# ALU.net
KiCad netlist of a schematic drawn in EAGLE
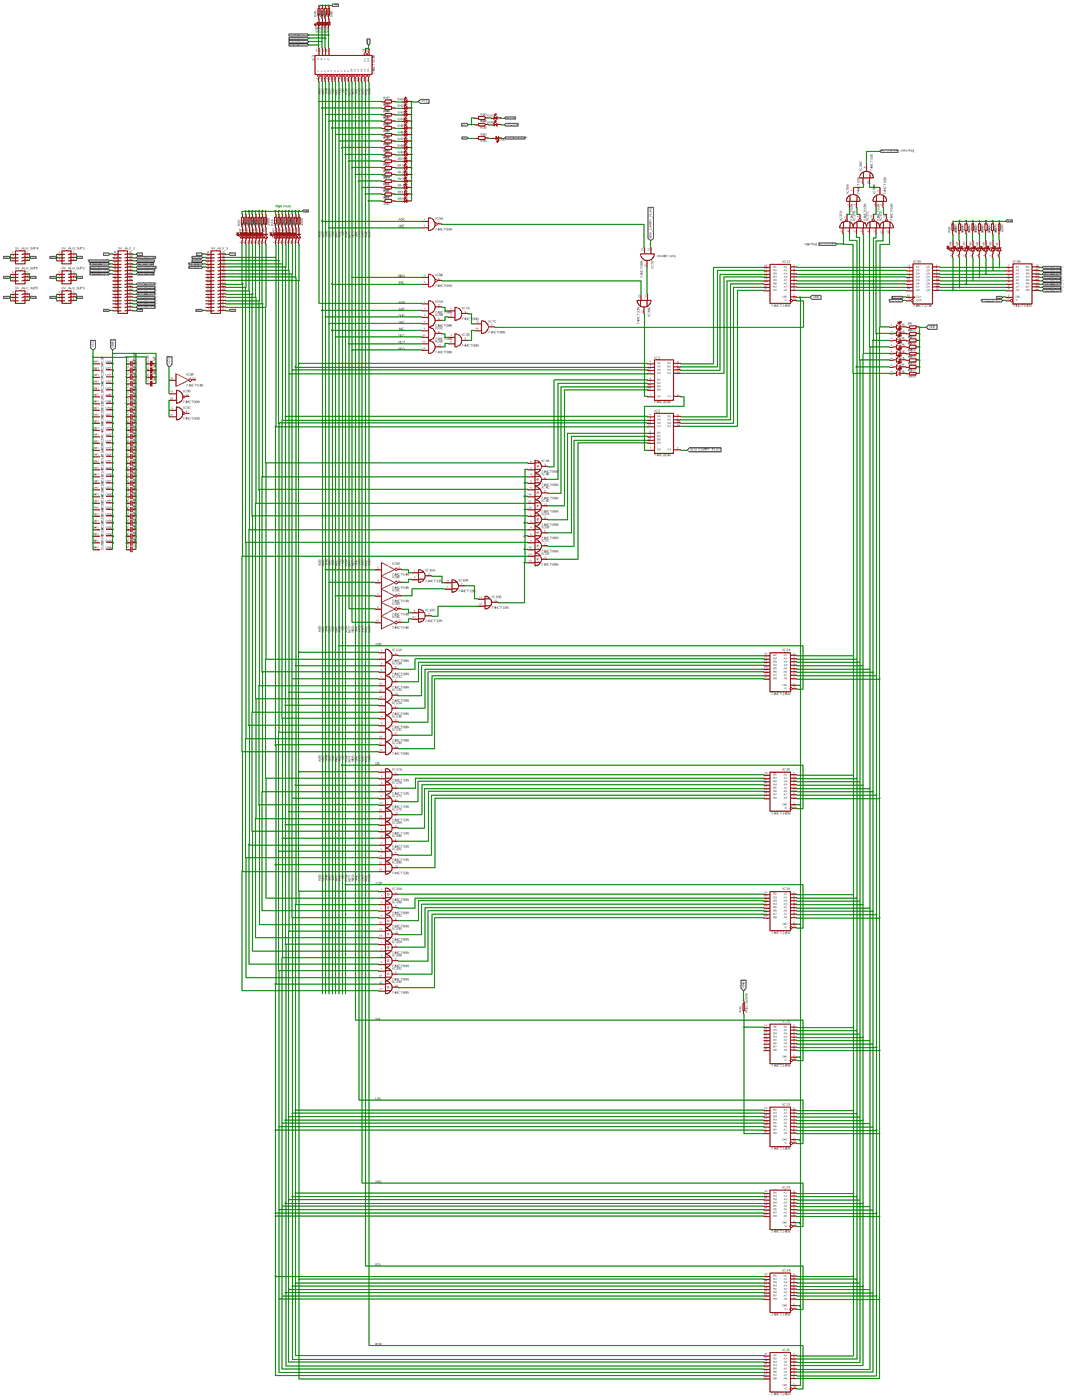
[diagram p0: schematic, sheet 1, overview]
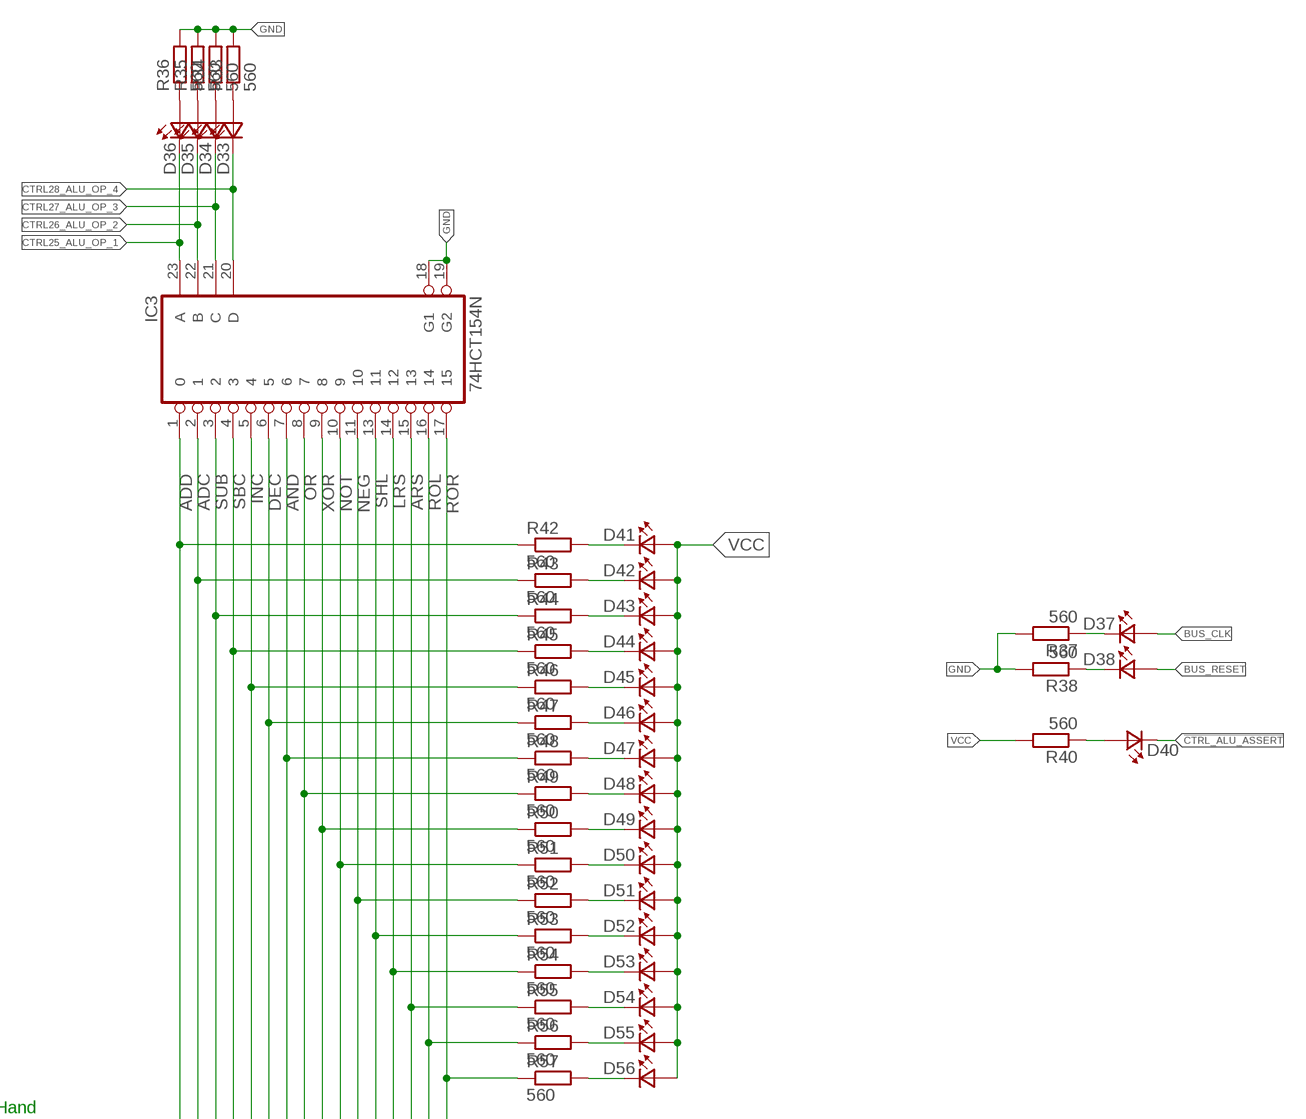
[diagram p1: schematic, sheet 1, part 1 of 8]
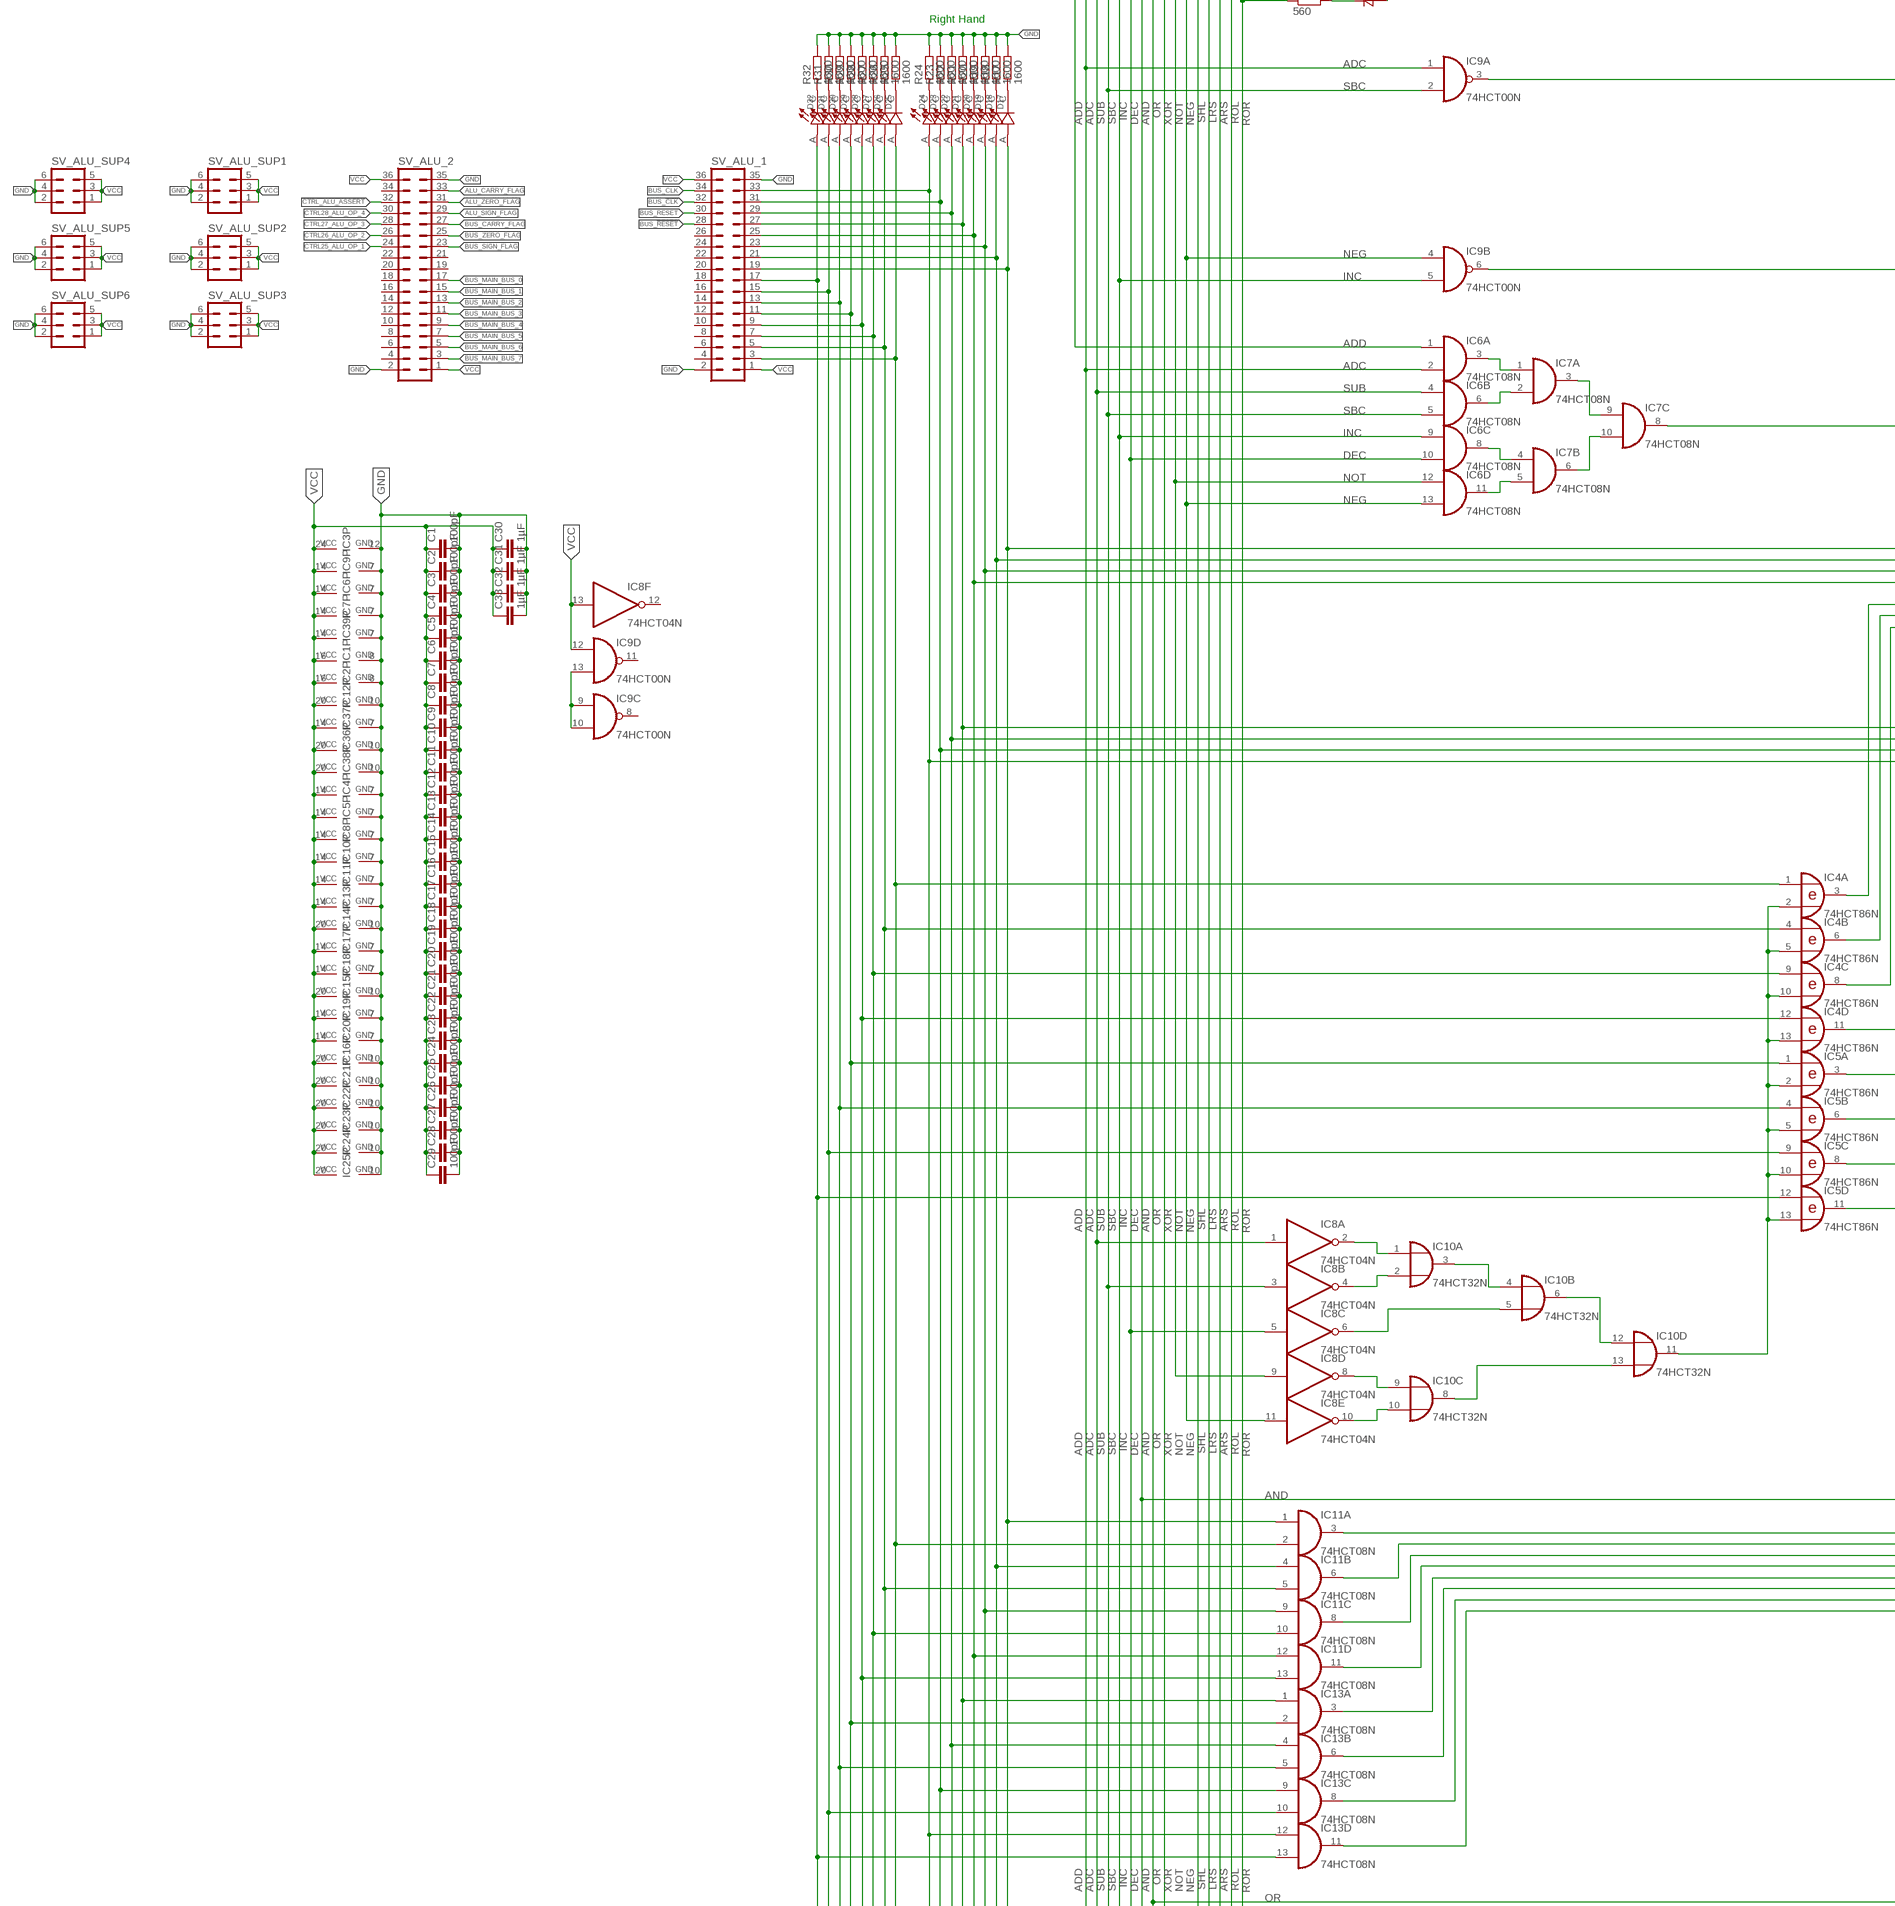
[diagram p2: schematic, sheet 1, part 2 of 8]
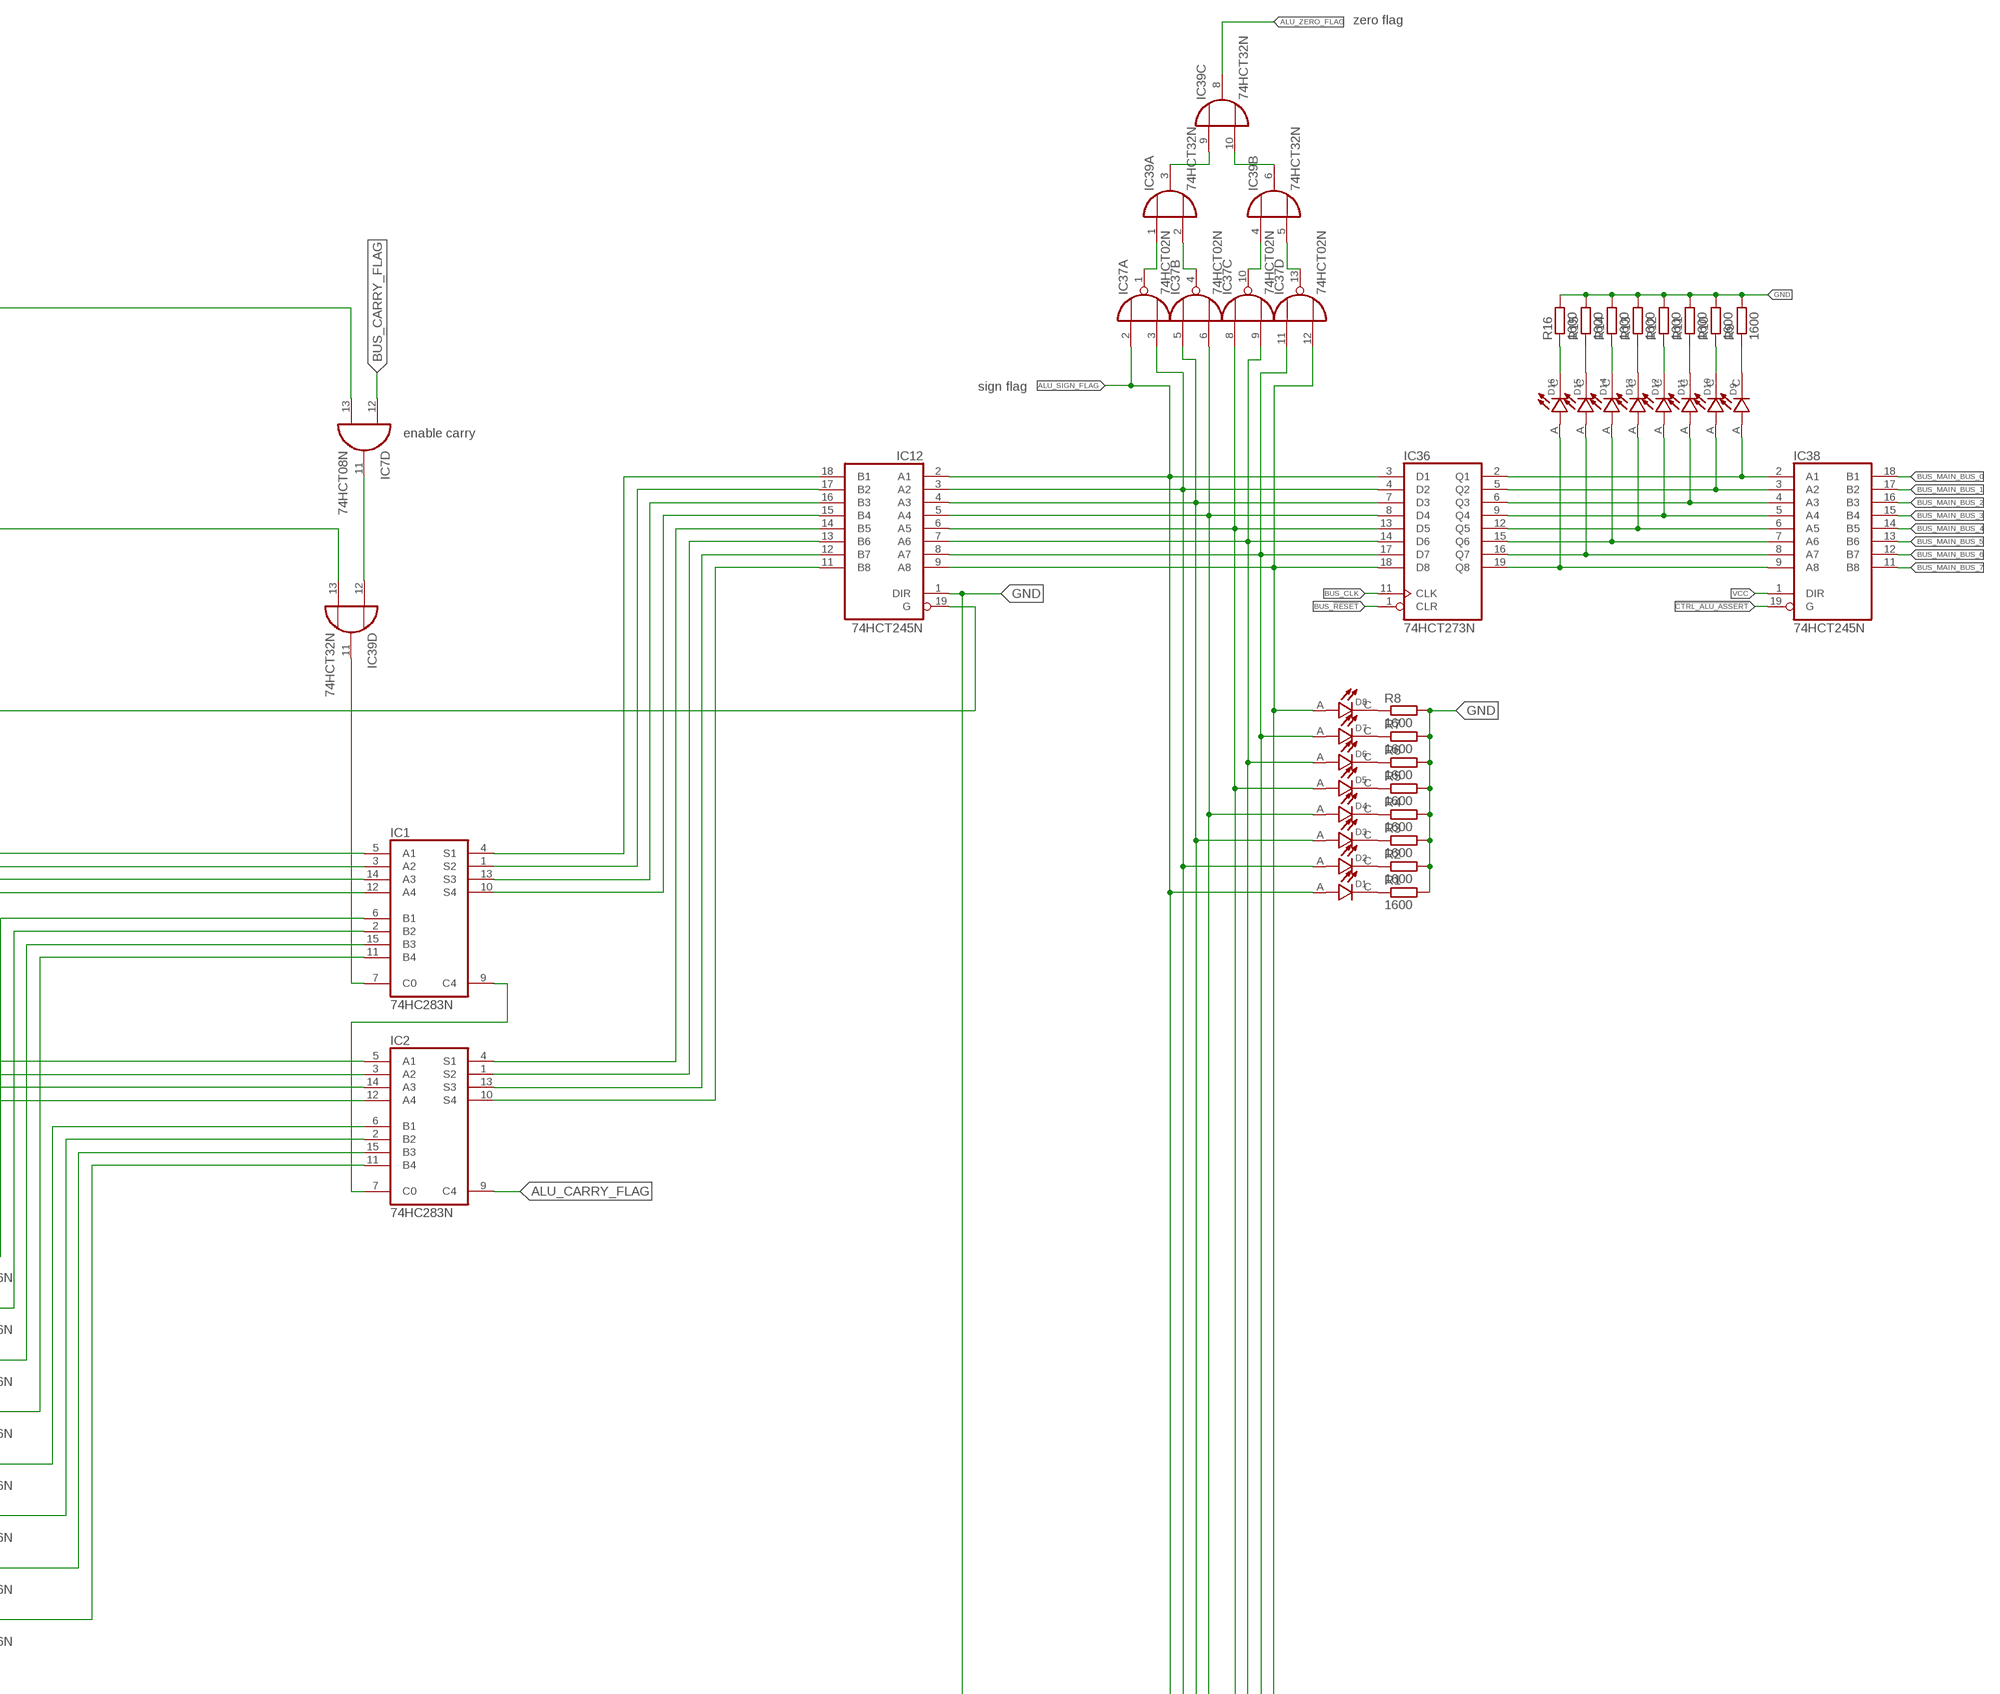
[diagram p3: schematic, sheet 1, part 3 of 8]
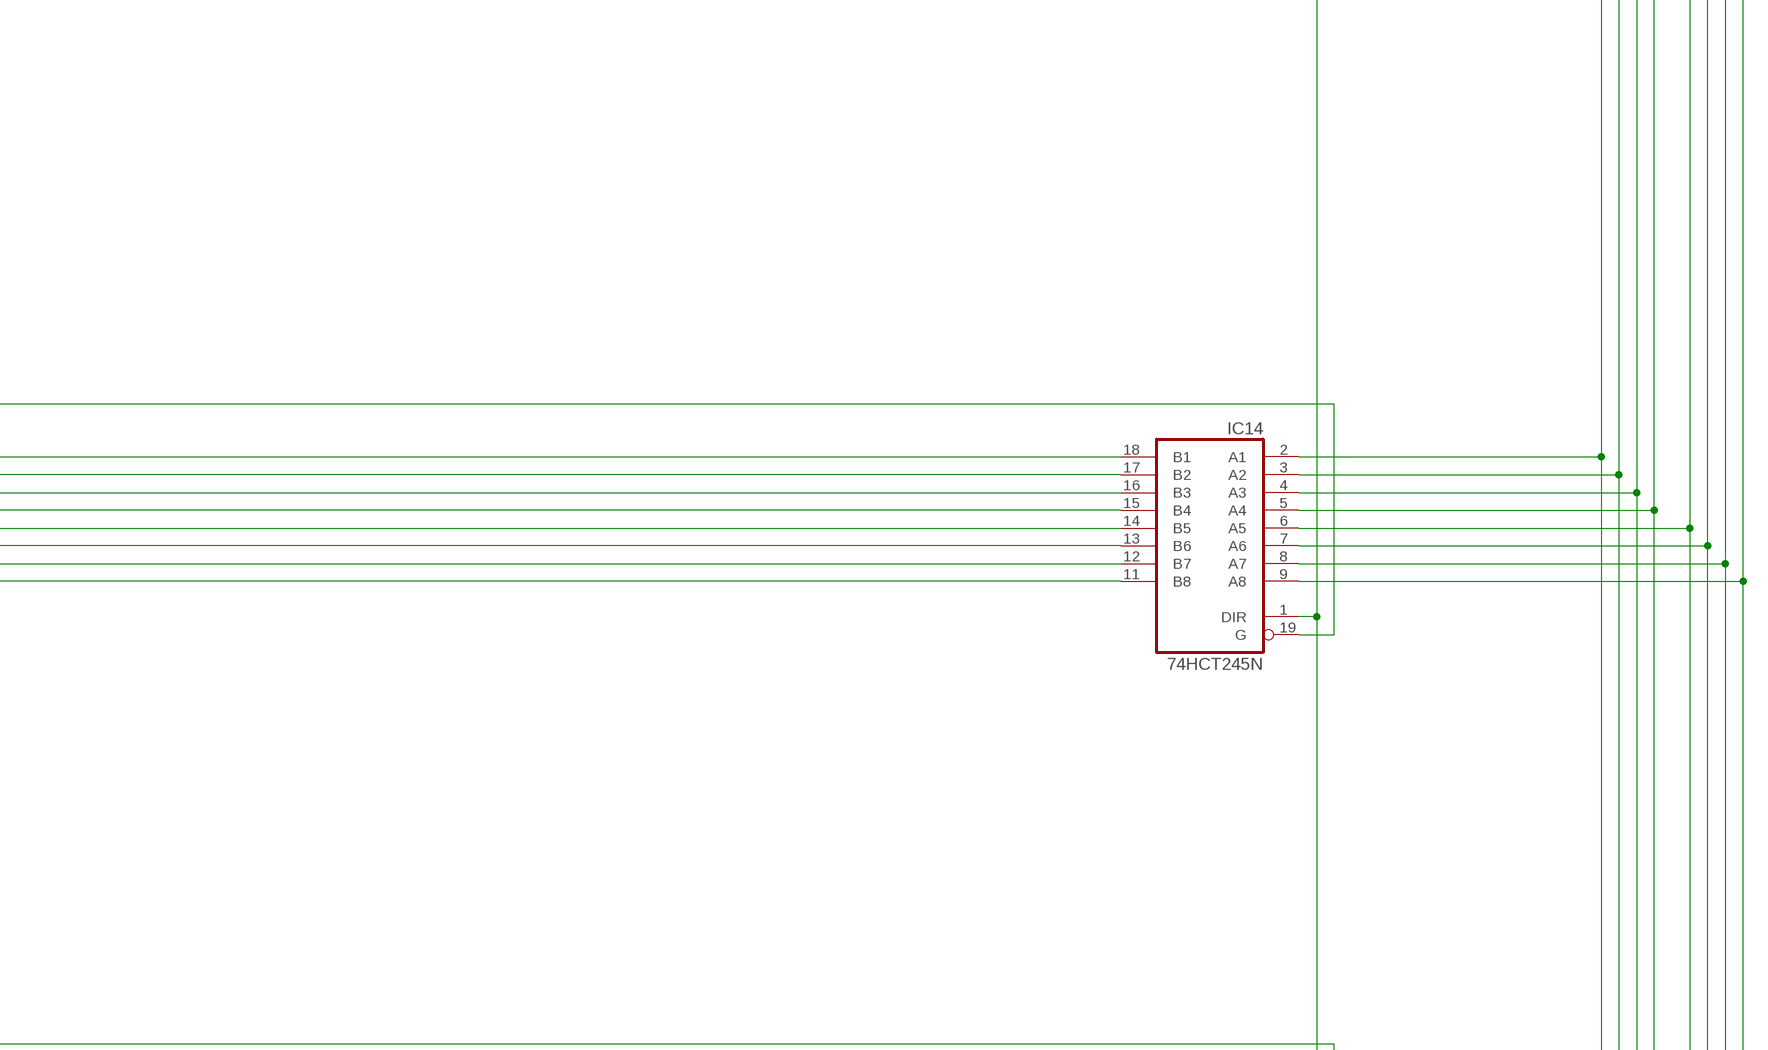
[diagram p4: schematic, sheet 1, part 4 of 8]
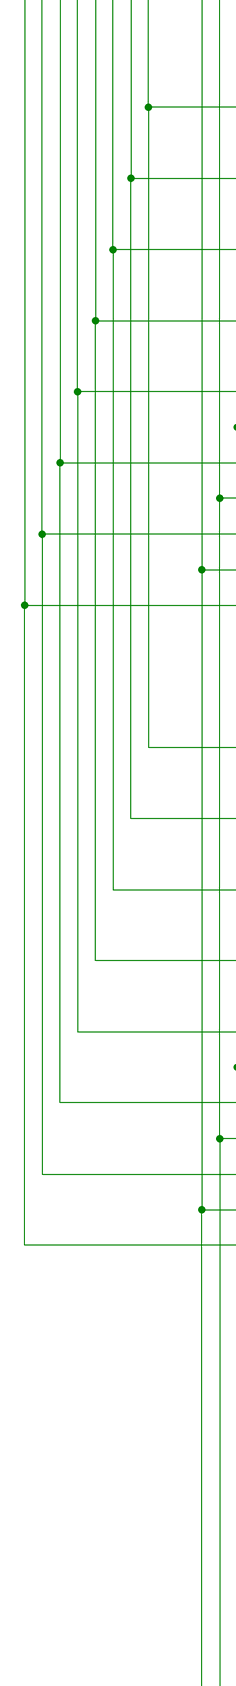
[diagram p5: schematic, sheet 1, part 5 of 8]
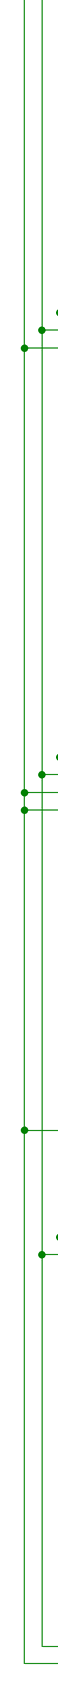
[diagram p6: schematic, sheet 1, part 6 of 8]
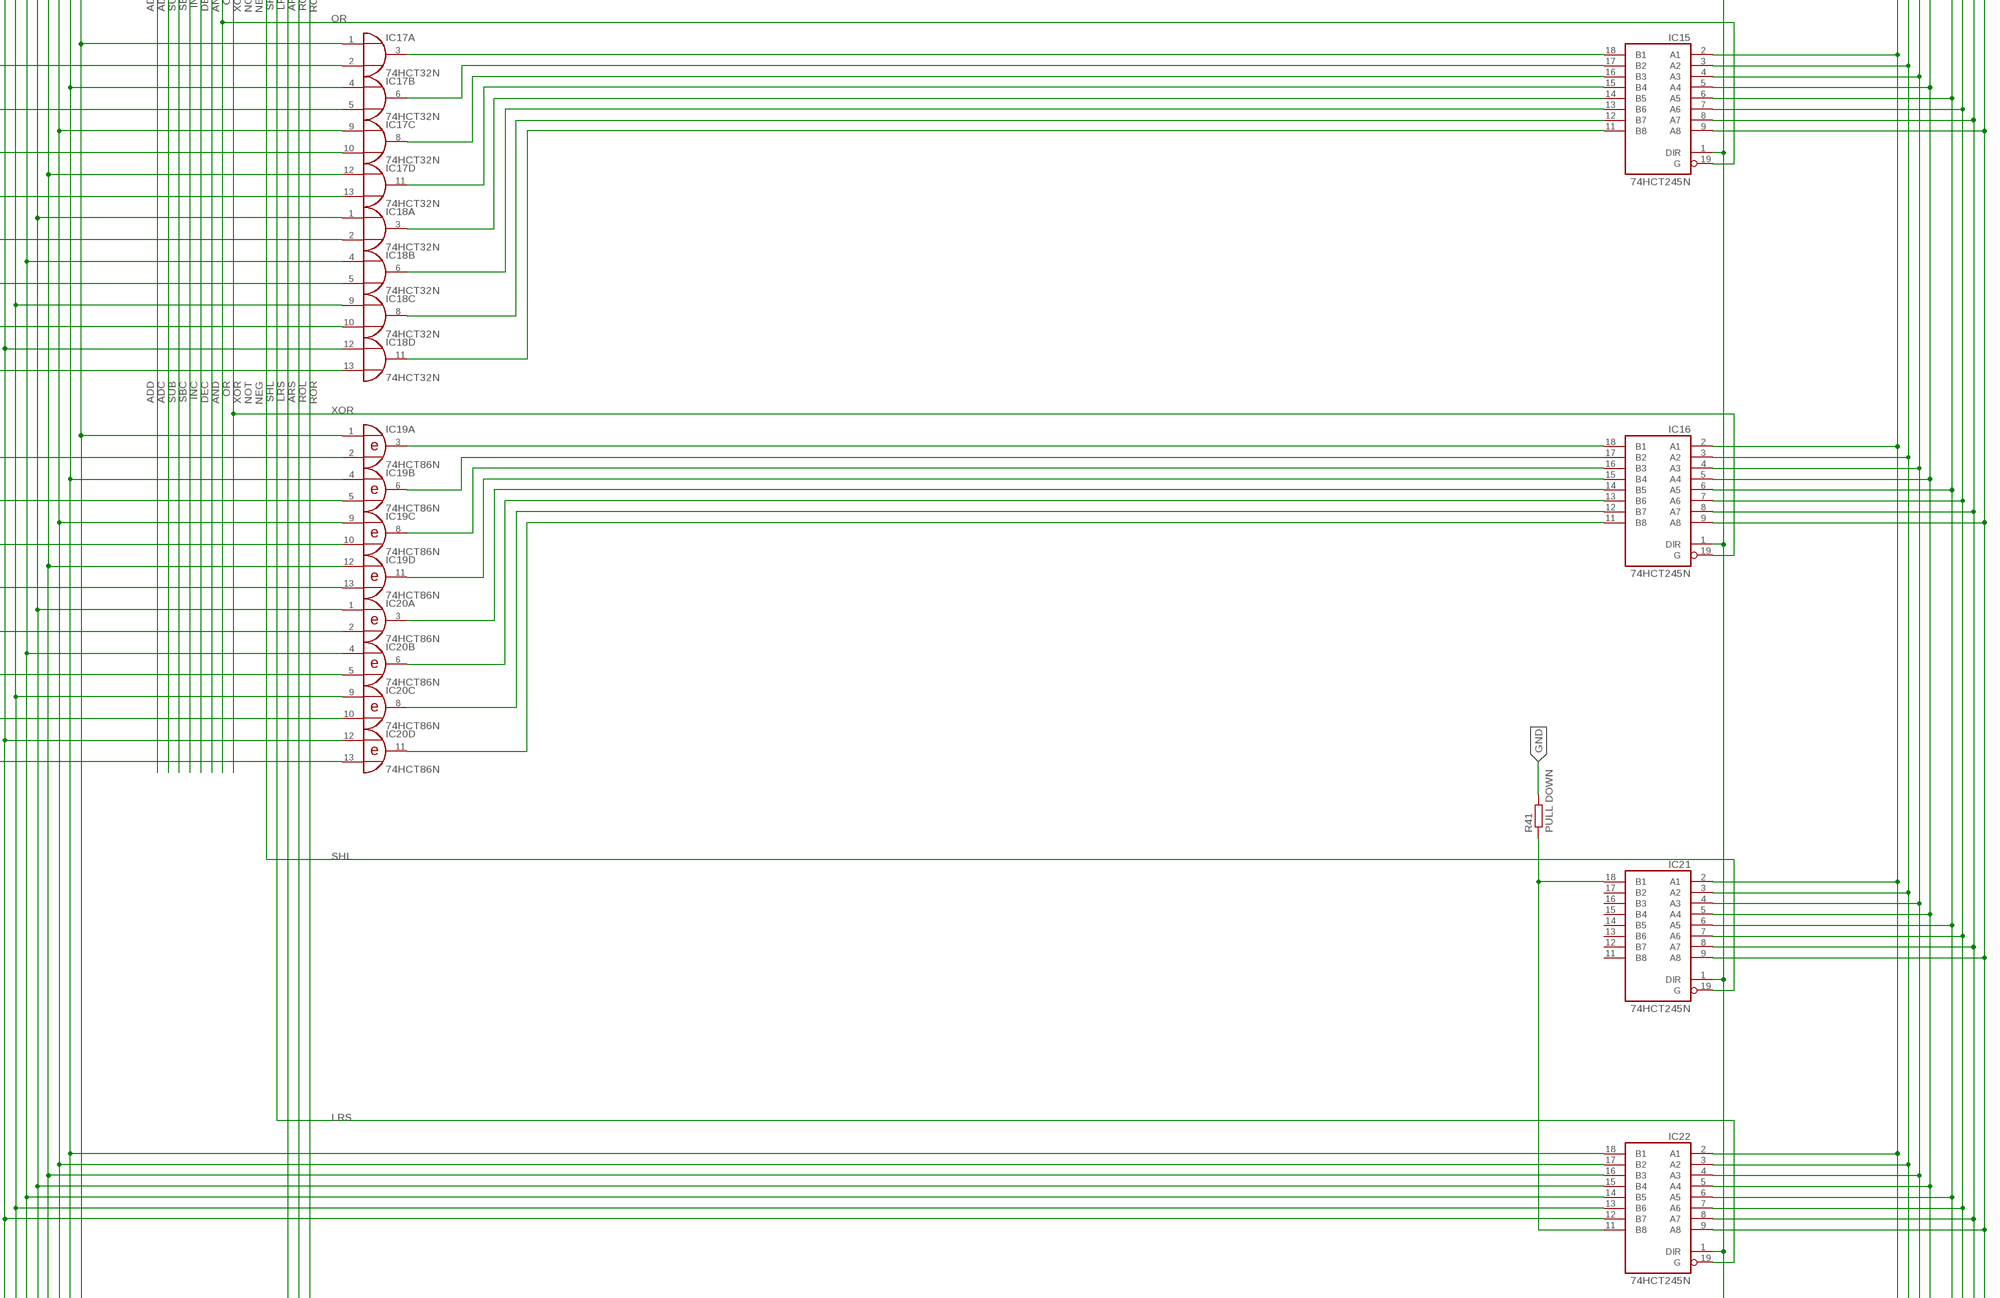
[diagram p7: schematic, sheet 1, part 7 of 8]
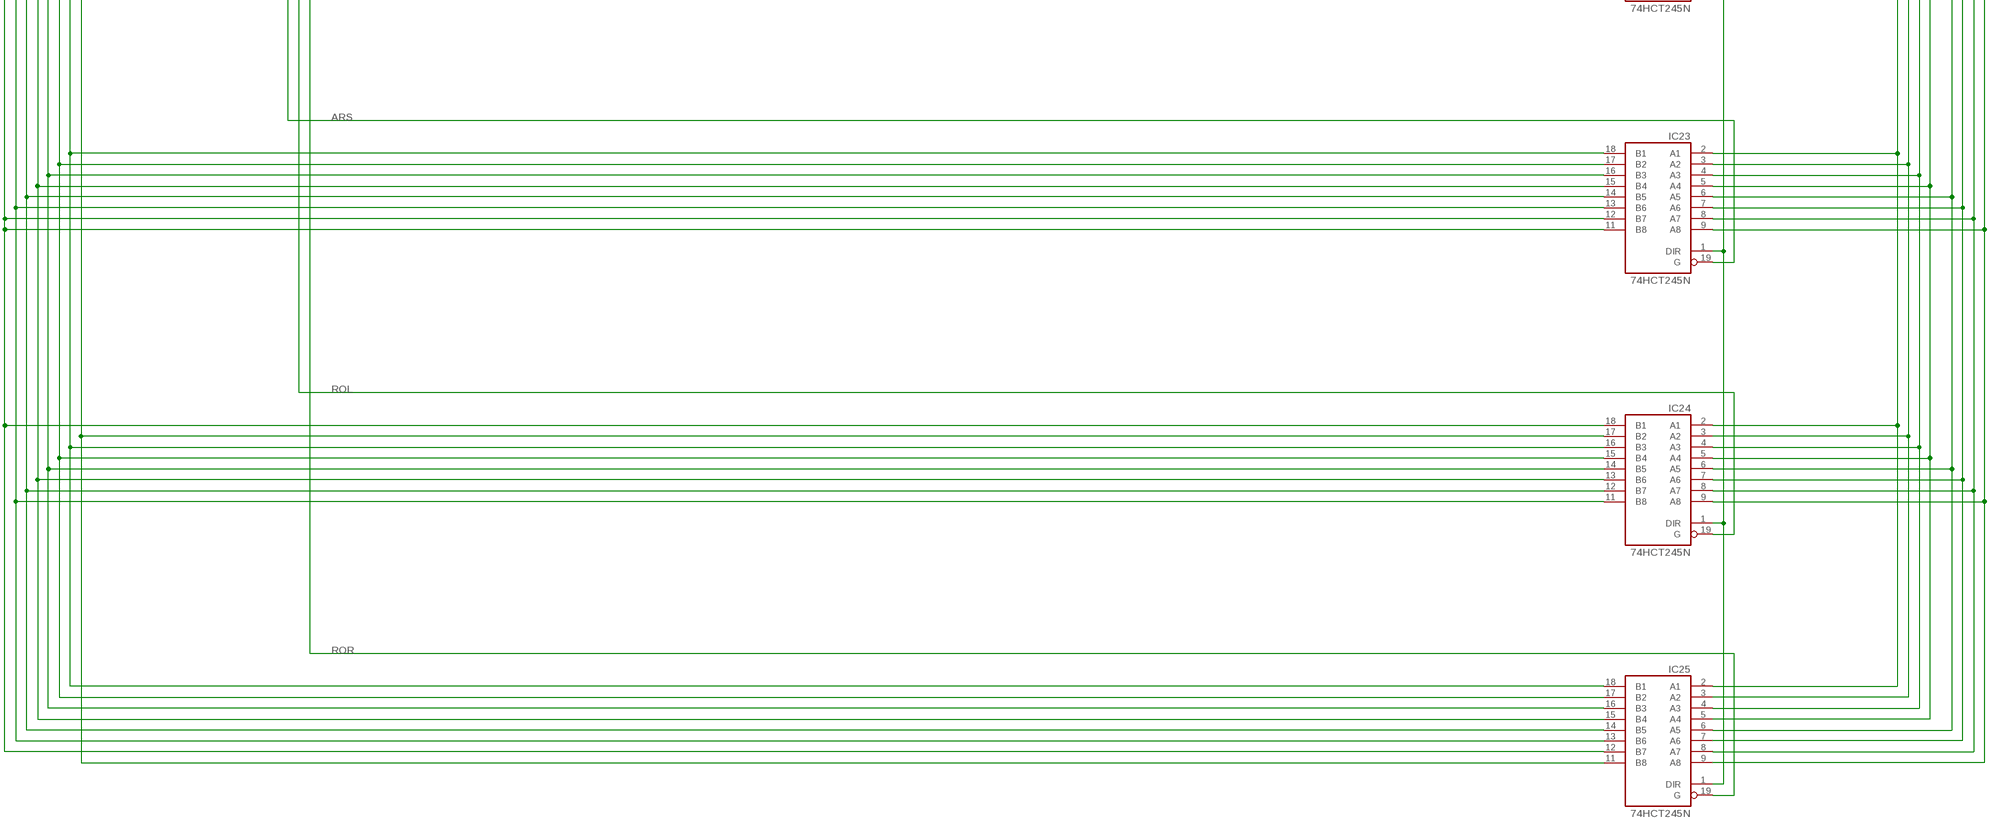
[diagram p8: schematic, sheet 1, part 8 of 8]

(export (version "E")
  (design (tool "Eeschema 10.0.6"))
  (components
    (comp (ref "C1")
      (value "100pF")
      (footprint "eagle-import:C0805")
      (libsource (lib "eagle-import") (part "C-EUC0805"))
    )
    (comp (ref "C2")
      (value "100pF")
      (footprint "eagle-import:C0805")
      (libsource (lib "eagle-import") (part "C-EUC0805"))
    )
    (comp (ref "C3")
      (value "100pF")
      (footprint "eagle-import:C0805")
      (libsource (lib "eagle-import") (part "C-EUC0805"))
    )
    (comp (ref "C4")
      (value "100pF")
      (footprint "eagle-import:C0805")
      (libsource (lib "eagle-import") (part "C-EUC0805"))
    )
    (comp (ref "C5")
      (value "100pF")
      (footprint "eagle-import:C0805")
      (libsource (lib "eagle-import") (part "C-EUC0805"))
    )
    (comp (ref "C6")
      (value "100pF")
      (footprint "eagle-import:C0805")
      (libsource (lib "eagle-import") (part "C-EUC0805"))
    )
    (comp (ref "C7")
      (value "100pF")
      (footprint "eagle-import:C0805")
      (libsource (lib "eagle-import") (part "C-EUC0805"))
    )
    (comp (ref "C8")
      (value "100pF")
      (footprint "eagle-import:C0805")
      (libsource (lib "eagle-import") (part "C-EUC0805"))
    )
    (comp (ref "C9")
      (value "100pF")
      (footprint "eagle-import:C0805")
      (libsource (lib "eagle-import") (part "C-EUC0805"))
    )
    (comp (ref "C10")
      (value "100pF")
      (footprint "eagle-import:C0805")
      (libsource (lib "eagle-import") (part "C-EUC0805"))
    )
    (comp (ref "C11")
      (value "100pF")
      (footprint "eagle-import:C0805")
      (libsource (lib "eagle-import") (part "C-EUC0805"))
    )
    (comp (ref "C12")
      (value "100pF")
      (footprint "eagle-import:C0805")
      (libsource (lib "eagle-import") (part "C-EUC0805"))
    )
    (comp (ref "C13")
      (value "100pF")
      (footprint "eagle-import:C0805")
      (libsource (lib "eagle-import") (part "C-EUC0805"))
    )
    (comp (ref "C14")
      (value "100pF")
      (footprint "eagle-import:C0805")
      (libsource (lib "eagle-import") (part "C-EUC0805"))
    )
    (comp (ref "C15")
      (value "100pF")
      (footprint "eagle-import:C0805")
      (libsource (lib "eagle-import") (part "C-EUC0805"))
    )
    (comp (ref "C16")
      (value "100pF")
      (footprint "eagle-import:C0805")
      (libsource (lib "eagle-import") (part "C-EUC0805"))
    )
    (comp (ref "C17")
      (value "100pF")
      (footprint "eagle-import:C0805")
      (libsource (lib "eagle-import") (part "C-EUC0805"))
    )
    (comp (ref "C18")
      (value "100pF")
      (footprint "eagle-import:C0805")
      (libsource (lib "eagle-import") (part "C-EUC0805"))
    )
    (comp (ref "C19")
      (value "100pF")
      (footprint "eagle-import:C0805")
      (libsource (lib "eagle-import") (part "C-EUC0805"))
    )
    (comp (ref "C20")
      (value "100pF")
      (footprint "eagle-import:C0805")
      (libsource (lib "eagle-import") (part "C-EUC0805"))
    )
    (comp (ref "C21")
      (value "100pF")
      (footprint "eagle-import:C0805")
      (libsource (lib "eagle-import") (part "C-EUC0805"))
    )
    (comp (ref "C22")
      (value "100pF")
      (footprint "eagle-import:C0805")
      (libsource (lib "eagle-import") (part "C-EUC0805"))
    )
    (comp (ref "C23")
      (value "100pF")
      (footprint "eagle-import:C0805")
      (libsource (lib "eagle-import") (part "C-EUC0805"))
    )
    (comp (ref "C24")
      (value "100pF")
      (footprint "eagle-import:C0805")
      (libsource (lib "eagle-import") (part "C-EUC0805"))
    )
    (comp (ref "C25")
      (value "100pF")
      (footprint "eagle-import:C0805")
      (libsource (lib "eagle-import") (part "C-EUC0805"))
    )
    (comp (ref "C26")
      (value "100pF")
      (footprint "eagle-import:C0805")
      (libsource (lib "eagle-import") (part "C-EUC0805"))
    )
    (comp (ref "C27")
      (value "100pF")
      (footprint "eagle-import:C0805")
      (libsource (lib "eagle-import") (part "C-EUC0805"))
    )
    (comp (ref "C28")
      (value "100pF")
      (footprint "eagle-import:C0805")
      (libsource (lib "eagle-import") (part "C-EUC0805"))
    )
    (comp (ref "C29")
      (value "100pF")
      (footprint "eagle-import:C0805")
      (libsource (lib "eagle-import") (part "C-EUC0805"))
    )
    (comp (ref "C30")
      (value "1µF")
      (footprint "eagle-import:C0805")
      (libsource (lib "eagle-import") (part "C-EUC0805"))
    )
    (comp (ref "C31")
      (value "1µF")
      (footprint "eagle-import:C0805")
      (libsource (lib "eagle-import") (part "C-EUC0805"))
    )
    (comp (ref "C32")
      (value "1µF")
      (footprint "eagle-import:C0805")
      (libsource (lib "eagle-import") (part "C-EUC0805"))
    )
    (comp (ref "C33")
      (value "1µF")
      (footprint "eagle-import:C0805")
      (libsource (lib "eagle-import") (part "C-EUC0805"))
    )
    (comp (ref "D1")
      (value "LTST-C193KRKT-5A")
      (footprint "eagle-import:LEDC1608X45N")
      (fields (field (name "MANUFACTURER") "Lite-On"))
      (libsource (lib "eagle-import") (part "LTST-C193KRKT-5A"))
    )
    (comp (ref "D2")
      (value "LTST-C193KRKT-5A")
      (footprint "eagle-import:LEDC1608X45N")
      (fields (field (name "MANUFACTURER") "Lite-On"))
      (libsource (lib "eagle-import") (part "LTST-C193KRKT-5A"))
    )
    (comp (ref "D3")
      (value "LTST-C193KRKT-5A")
      (footprint "eagle-import:LEDC1608X45N")
      (fields (field (name "MANUFACTURER") "Lite-On"))
      (libsource (lib "eagle-import") (part "LTST-C193KRKT-5A"))
    )
    (comp (ref "D4")
      (value "LTST-C193KRKT-5A")
      (footprint "eagle-import:LEDC1608X45N")
      (fields (field (name "MANUFACTURER") "Lite-On"))
      (libsource (lib "eagle-import") (part "LTST-C193KRKT-5A"))
    )
    (comp (ref "D5")
      (value "LTST-C193KRKT-5A")
      (footprint "eagle-import:LEDC1608X45N")
      (fields (field (name "MANUFACTURER") "Lite-On"))
      (libsource (lib "eagle-import") (part "LTST-C193KRKT-5A"))
    )
    (comp (ref "D6")
      (value "LTST-C193KRKT-5A")
      (footprint "eagle-import:LEDC1608X45N")
      (fields (field (name "MANUFACTURER") "Lite-On"))
      (libsource (lib "eagle-import") (part "LTST-C193KRKT-5A"))
    )
    (comp (ref "D7")
      (value "LTST-C193KRKT-5A")
      (footprint "eagle-import:LEDC1608X45N")
      (fields (field (name "MANUFACTURER") "Lite-On"))
      (libsource (lib "eagle-import") (part "LTST-C193KRKT-5A"))
    )
    (comp (ref "D8")
      (value "LTST-C193KRKT-5A")
      (footprint "eagle-import:LEDC1608X45N")
      (fields (field (name "MANUFACTURER") "Lite-On"))
      (libsource (lib "eagle-import") (part "LTST-C193KRKT-5A"))
    )
    (comp (ref "D9")
      (value "LTST-C193KRKT-5A")
      (footprint "eagle-import:LEDC1608X45N")
      (fields (field (name "MANUFACTURER") "Lite-On"))
      (libsource (lib "eagle-import") (part "LTST-C193KRKT-5A"))
    )
    (comp (ref "D10")
      (value "LTST-C193KRKT-5A")
      (footprint "eagle-import:LEDC1608X45N")
      (fields (field (name "MANUFACTURER") "Lite-On"))
      (libsource (lib "eagle-import") (part "LTST-C193KRKT-5A"))
    )
    (comp (ref "D11")
      (value "LTST-C193KRKT-5A")
      (footprint "eagle-import:LEDC1608X45N")
      (fields (field (name "MANUFACTURER") "Lite-On"))
      (libsource (lib "eagle-import") (part "LTST-C193KRKT-5A"))
    )
    (comp (ref "D12")
      (value "LTST-C193KRKT-5A")
      (footprint "eagle-import:LEDC1608X45N")
      (fields (field (name "MANUFACTURER") "Lite-On"))
      (libsource (lib "eagle-import") (part "LTST-C193KRKT-5A"))
    )
    (comp (ref "D13")
      (value "LTST-C193KRKT-5A")
      (footprint "eagle-import:LEDC1608X45N")
      (fields (field (name "MANUFACTURER") "Lite-On"))
      (libsource (lib "eagle-import") (part "LTST-C193KRKT-5A"))
    )
    (comp (ref "D14")
      (value "LTST-C193KRKT-5A")
      (footprint "eagle-import:LEDC1608X45N")
      (fields (field (name "MANUFACTURER") "Lite-On"))
      (libsource (lib "eagle-import") (part "LTST-C193KRKT-5A"))
    )
    (comp (ref "D15")
      (value "LTST-C193KRKT-5A")
      (footprint "eagle-import:LEDC1608X45N")
      (fields (field (name "MANUFACTURER") "Lite-On"))
      (libsource (lib "eagle-import") (part "LTST-C193KRKT-5A"))
    )
    (comp (ref "D16")
      (value "LTST-C193KRKT-5A")
      (footprint "eagle-import:LEDC1608X45N")
      (fields (field (name "MANUFACTURER") "Lite-On"))
      (libsource (lib "eagle-import") (part "LTST-C193KRKT-5A"))
    )
    (comp (ref "D17")
      (value "LTST-C193KRKT-5A")
      (footprint "eagle-import:LEDC1608X45N")
      (fields (field (name "MANUFACTURER") "Lite-On"))
      (libsource (lib "eagle-import") (part "LTST-C193KRKT-5A"))
    )
    (comp (ref "D18")
      (value "LTST-C193KRKT-5A")
      (footprint "eagle-import:LEDC1608X45N")
      (fields (field (name "MANUFACTURER") "Lite-On"))
      (libsource (lib "eagle-import") (part "LTST-C193KRKT-5A"))
    )
    (comp (ref "D19")
      (value "LTST-C193KRKT-5A")
      (footprint "eagle-import:LEDC1608X45N")
      (fields (field (name "MANUFACTURER") "Lite-On"))
      (libsource (lib "eagle-import") (part "LTST-C193KRKT-5A"))
    )
    (comp (ref "D20")
      (value "LTST-C193KRKT-5A")
      (footprint "eagle-import:LEDC1608X45N")
      (fields (field (name "MANUFACTURER") "Lite-On"))
      (libsource (lib "eagle-import") (part "LTST-C193KRKT-5A"))
    )
    (comp (ref "D21")
      (value "LTST-C193KRKT-5A")
      (footprint "eagle-import:LEDC1608X45N")
      (fields (field (name "MANUFACTURER") "Lite-On"))
      (libsource (lib "eagle-import") (part "LTST-C193KRKT-5A"))
    )
    (comp (ref "D22")
      (value "LTST-C193KRKT-5A")
      (footprint "eagle-import:LEDC1608X45N")
      (fields (field (name "MANUFACTURER") "Lite-On"))
      (libsource (lib "eagle-import") (part "LTST-C193KRKT-5A"))
    )
    (comp (ref "D23")
      (value "LTST-C193KRKT-5A")
      (footprint "eagle-import:LEDC1608X45N")
      (fields (field (name "MANUFACTURER") "Lite-On"))
      (libsource (lib "eagle-import") (part "LTST-C193KRKT-5A"))
    )
    (comp (ref "D24")
      (value "LTST-C193KRKT-5A")
      (footprint "eagle-import:LEDC1608X45N")
      (fields (field (name "MANUFACTURER") "Lite-On"))
      (libsource (lib "eagle-import") (part "LTST-C193KRKT-5A"))
    )
    (comp (ref "D25")
      (value "LTST-C193KRKT-5A")
      (footprint "eagle-import:LEDC1608X45N")
      (fields (field (name "MANUFACTURER") "Lite-On"))
      (libsource (lib "eagle-import") (part "LTST-C193KRKT-5A"))
    )
    (comp (ref "D26")
      (value "LTST-C193KRKT-5A")
      (footprint "eagle-import:LEDC1608X45N")
      (fields (field (name "MANUFACTURER") "Lite-On"))
      (libsource (lib "eagle-import") (part "LTST-C193KRKT-5A"))
    )
    (comp (ref "D27")
      (value "LTST-C193KRKT-5A")
      (footprint "eagle-import:LEDC1608X45N")
      (fields (field (name "MANUFACTURER") "Lite-On"))
      (libsource (lib "eagle-import") (part "LTST-C193KRKT-5A"))
    )
    (comp (ref "D28")
      (value "LTST-C193KRKT-5A")
      (footprint "eagle-import:LEDC1608X45N")
      (fields (field (name "MANUFACTURER") "Lite-On"))
      (libsource (lib "eagle-import") (part "LTST-C193KRKT-5A"))
    )
    (comp (ref "D29")
      (value "LTST-C193KRKT-5A")
      (footprint "eagle-import:LEDC1608X45N")
      (fields (field (name "MANUFACTURER") "Lite-On"))
      (libsource (lib "eagle-import") (part "LTST-C193KRKT-5A"))
    )
    (comp (ref "D30")
      (value "LTST-C193KRKT-5A")
      (footprint "eagle-import:LEDC1608X45N")
      (fields (field (name "MANUFACTURER") "Lite-On"))
      (libsource (lib "eagle-import") (part "LTST-C193KRKT-5A"))
    )
    (comp (ref "D31")
      (value "LTST-C193KRKT-5A")
      (footprint "eagle-import:LEDC1608X45N")
      (fields (field (name "MANUFACTURER") "Lite-On"))
      (libsource (lib "eagle-import") (part "LTST-C193KRKT-5A"))
    )
    (comp (ref "D32")
      (value "LTST-C193KRKT-5A")
      (footprint "eagle-import:LEDC1608X45N")
      (fields (field (name "MANUFACTURER") "Lite-On"))
      (libsource (lib "eagle-import") (part "LTST-C193KRKT-5A"))
    )
    (comp (ref "D33")
      (value "LTST-C193TBKT-5A")
      (footprint "eagle-import:0603")
      (libsource (lib "eagle-import") (part "LTST-C193TBKT-5A"))
    )
    (comp (ref "D34")
      (value "LTST-C193TBKT-5A")
      (footprint "eagle-import:0603")
      (libsource (lib "eagle-import") (part "LTST-C193TBKT-5A"))
    )
    (comp (ref "D35")
      (value "LTST-C193TBKT-5A")
      (footprint "eagle-import:0603")
      (libsource (lib "eagle-import") (part "LTST-C193TBKT-5A"))
    )
    (comp (ref "D36")
      (value "LTST-C193TBKT-5A")
      (footprint "eagle-import:0603")
      (libsource (lib "eagle-import") (part "LTST-C193TBKT-5A"))
    )
    (comp (ref "D37")
      (value "LTST-C193TBKT-5A")
      (footprint "eagle-import:0603")
      (libsource (lib "eagle-import") (part "LTST-C193TBKT-5A"))
    )
    (comp (ref "D38")
      (value "LTST-C193TBKT-5A")
      (footprint "eagle-import:0603")
      (libsource (lib "eagle-import") (part "LTST-C193TBKT-5A"))
    )
    (comp (ref "D40")
      (value "LTST-C193TBKT-5A")
      (footprint "eagle-import:0603")
      (libsource (lib "eagle-import") (part "LTST-C193TBKT-5A"))
    )
    (comp (ref "D41")
      (value "LTST-C193TBKT-5A")
      (footprint "eagle-import:0603")
      (libsource (lib "eagle-import") (part "LTST-C193TBKT-5A"))
    )
    (comp (ref "D42")
      (value "LTST-C193TBKT-5A")
      (footprint "eagle-import:0603")
      (libsource (lib "eagle-import") (part "LTST-C193TBKT-5A"))
    )
    (comp (ref "D43")
      (value "LTST-C193TBKT-5A")
      (footprint "eagle-import:0603")
      (libsource (lib "eagle-import") (part "LTST-C193TBKT-5A"))
    )
    (comp (ref "D44")
      (value "LTST-C193TBKT-5A")
      (footprint "eagle-import:0603")
      (libsource (lib "eagle-import") (part "LTST-C193TBKT-5A"))
    )
    (comp (ref "D45")
      (value "LTST-C193TBKT-5A")
      (footprint "eagle-import:0603")
      (libsource (lib "eagle-import") (part "LTST-C193TBKT-5A"))
    )
    (comp (ref "D46")
      (value "LTST-C193TBKT-5A")
      (footprint "eagle-import:0603")
      (libsource (lib "eagle-import") (part "LTST-C193TBKT-5A"))
    )
    (comp (ref "D47")
      (value "LTST-C193TBKT-5A")
      (footprint "eagle-import:0603")
      (libsource (lib "eagle-import") (part "LTST-C193TBKT-5A"))
    )
    (comp (ref "D48")
      (value "LTST-C193TBKT-5A")
      (footprint "eagle-import:0603")
      (libsource (lib "eagle-import") (part "LTST-C193TBKT-5A"))
    )
    (comp (ref "D49")
      (value "LTST-C193TBKT-5A")
      (footprint "eagle-import:0603")
      (libsource (lib "eagle-import") (part "LTST-C193TBKT-5A"))
    )
    (comp (ref "D50")
      (value "LTST-C193TBKT-5A")
      (footprint "eagle-import:0603")
      (libsource (lib "eagle-import") (part "LTST-C193TBKT-5A"))
    )
    (comp (ref "D51")
      (value "LTST-C193TBKT-5A")
      (footprint "eagle-import:0603")
      (libsource (lib "eagle-import") (part "LTST-C193TBKT-5A"))
    )
    (comp (ref "D52")
      (value "LTST-C193TBKT-5A")
      (footprint "eagle-import:0603")
      (libsource (lib "eagle-import") (part "LTST-C193TBKT-5A"))
    )
    (comp (ref "D53")
      (value "LTST-C193TBKT-5A")
      (footprint "eagle-import:0603")
      (libsource (lib "eagle-import") (part "LTST-C193TBKT-5A"))
    )
    (comp (ref "D54")
      (value "LTST-C193TBKT-5A")
      (footprint "eagle-import:0603")
      (libsource (lib "eagle-import") (part "LTST-C193TBKT-5A"))
    )
    (comp (ref "D55")
      (value "LTST-C193TBKT-5A")
      (footprint "eagle-import:0603")
      (libsource (lib "eagle-import") (part "LTST-C193TBKT-5A"))
    )
    (comp (ref "D56")
      (value "LTST-C193TBKT-5A")
      (footprint "eagle-import:0603")
      (libsource (lib "eagle-import") (part "LTST-C193TBKT-5A"))
    )
    (comp (ref "IC1")
      (value "74HC283N")
      (footprint "eagle-import:DIL16")
      (libsource (lib "eagle-import") (part "74283NHC"))
    )
    (comp (ref "IC2")
      (value "74HC283N")
      (footprint "eagle-import:DIL16")
      (libsource (lib "eagle-import") (part "74283NHC"))
    )
    (comp (ref "IC3")
      (value "74HCT154N")
      (footprint "eagle-import:DIL24-6")
      (libsource (lib "eagle-import") (part "74154NHCT"))
    )
    (comp (ref "IC4")
      (value "74HCT86N")
      (footprint "eagle-import:DIL14")
      (libsource (lib "eagle-import") (part "7486NHCT"))
    )
    (comp (ref "IC5")
      (value "74HCT86N")
      (footprint "eagle-import:DIL14")
      (libsource (lib "eagle-import") (part "7486NHCT"))
    )
    (comp (ref "IC6")
      (value "74HCT08N")
      (footprint "eagle-import:DIL14")
      (libsource (lib "eagle-import") (part "7408NHCT"))
    )
    (comp (ref "IC7")
      (value "74HCT08N")
      (footprint "eagle-import:DIL14")
      (libsource (lib "eagle-import") (part "7408NHCT"))
    )
    (comp (ref "IC8")
      (value "74HCT04N")
      (footprint "eagle-import:DIL14")
      (libsource (lib "eagle-import") (part "7404NHCT"))
    )
    (comp (ref "IC9")
      (value "74HCT00N")
      (footprint "eagle-import:DIL14")
      (libsource (lib "eagle-import") (part "7400NHCT"))
    )
    (comp (ref "IC10")
      (value "74HCT32N")
      (footprint "eagle-import:DIL14")
      (libsource (lib "eagle-import") (part "7432NHCT"))
    )
    (comp (ref "IC11")
      (value "74HCT08N")
      (footprint "eagle-import:DIL14")
      (libsource (lib "eagle-import") (part "7408NHCT"))
    )
    (comp (ref "IC12")
      (value "74HCT245N")
      (footprint "eagle-import:DIL20")
      (libsource (lib "eagle-import") (part "74245NHCT"))
    )
    (comp (ref "IC13")
      (value "74HCT08N")
      (footprint "eagle-import:DIL14")
      (libsource (lib "eagle-import") (part "7408NHCT"))
    )
    (comp (ref "IC14")
      (value "74HCT245N")
      (footprint "eagle-import:DIL20")
      (libsource (lib "eagle-import") (part "74245NHCT"))
    )
    (comp (ref "IC15")
      (value "74HCT245N")
      (footprint "eagle-import:DIL20")
      (libsource (lib "eagle-import") (part "74245NHCT"))
    )
    (comp (ref "IC16")
      (value "74HCT245N")
      (footprint "eagle-import:DIL20")
      (libsource (lib "eagle-import") (part "74245NHCT"))
    )
    (comp (ref "IC17")
      (value "74HCT32N")
      (footprint "eagle-import:DIL14")
      (libsource (lib "eagle-import") (part "7432NHCT"))
    )
    (comp (ref "IC18")
      (value "74HCT32N")
      (footprint "eagle-import:DIL14")
      (libsource (lib "eagle-import") (part "7432NHCT"))
    )
    (comp (ref "IC19")
      (value "74HCT86N")
      (footprint "eagle-import:DIL14")
      (libsource (lib "eagle-import") (part "7486NHCT"))
    )
    (comp (ref "IC20")
      (value "74HCT86N")
      (footprint "eagle-import:DIL14")
      (libsource (lib "eagle-import") (part "7486NHCT"))
    )
    (comp (ref "IC21")
      (value "74HCT245N")
      (footprint "eagle-import:DIL20")
      (libsource (lib "eagle-import") (part "74245NHCT"))
    )
    (comp (ref "IC22")
      (value "74HCT245N")
      (footprint "eagle-import:DIL20")
      (libsource (lib "eagle-import") (part "74245NHCT"))
    )
    (comp (ref "IC23")
      (value "74HCT245N")
      (footprint "eagle-import:DIL20")
      (libsource (lib "eagle-import") (part "74245NHCT"))
    )
    (comp (ref "IC24")
      (value "74HCT245N")
      (footprint "eagle-import:DIL20")
      (libsource (lib "eagle-import") (part "74245NHCT"))
    )
    (comp (ref "IC25")
      (value "74HCT245N")
      (footprint "eagle-import:DIL20")
      (libsource (lib "eagle-import") (part "74245NHCT"))
    )
    (comp (ref "IC36")
      (value "74HCT273N")
      (footprint "eagle-import:DIL20")
      (libsource (lib "eagle-import") (part "74273NHCT"))
    )
    (comp (ref "IC37")
      (value "74HCT02N")
      (footprint "eagle-import:DIL14")
      (libsource (lib "eagle-import") (part "7402NHCT"))
    )
    (comp (ref "IC38")
      (value "74HCT245N")
      (footprint "eagle-import:DIL20")
      (libsource (lib "eagle-import") (part "74245NHCT"))
    )
    (comp (ref "IC39")
      (value "74HCT32N")
      (footprint "eagle-import:DIL14")
      (libsource (lib "eagle-import") (part "7432NHCT"))
    )
    (comp (ref "R1")
      (value "1600")
      (footprint "eagle-import:R0805")
      (libsource (lib "eagle-import") (part "R-EU_R0805"))
    )
    (comp (ref "R2")
      (value "1600")
      (footprint "eagle-import:R0805")
      (libsource (lib "eagle-import") (part "R-EU_R0805"))
    )
    (comp (ref "R3")
      (value "1600")
      (footprint "eagle-import:R0805")
      (libsource (lib "eagle-import") (part "R-EU_R0805"))
    )
    (comp (ref "R4")
      (value "1600")
      (footprint "eagle-import:R0805")
      (libsource (lib "eagle-import") (part "R-EU_R0805"))
    )
    (comp (ref "R5")
      (value "1600")
      (footprint "eagle-import:R0805")
      (libsource (lib "eagle-import") (part "R-EU_R0805"))
    )
    (comp (ref "R6")
      (value "1600")
      (footprint "eagle-import:R0805")
      (libsource (lib "eagle-import") (part "R-EU_R0805"))
    )
    (comp (ref "R7")
      (value "1600")
      (footprint "eagle-import:R0805")
      (libsource (lib "eagle-import") (part "R-EU_R0805"))
    )
    (comp (ref "R8")
      (value "1600")
      (footprint "eagle-import:R0805")
      (libsource (lib "eagle-import") (part "R-EU_R0805"))
    )
    (comp (ref "R9")
      (value "1600")
      (footprint "eagle-import:R0805")
      (libsource (lib "eagle-import") (part "R-EU_R0805"))
    )
    (comp (ref "R10")
      (value "1600")
      (footprint "eagle-import:R0805")
      (libsource (lib "eagle-import") (part "R-EU_R0805"))
    )
    (comp (ref "R11")
      (value "1600")
      (footprint "eagle-import:R0805")
      (libsource (lib "eagle-import") (part "R-EU_R0805"))
    )
    (comp (ref "R12")
      (value "1600")
      (footprint "eagle-import:R0805")
      (libsource (lib "eagle-import") (part "R-EU_R0805"))
    )
    (comp (ref "R13")
      (value "1600")
      (footprint "eagle-import:R0805")
      (libsource (lib "eagle-import") (part "R-EU_R0805"))
    )
    (comp (ref "R14")
      (value "1600")
      (footprint "eagle-import:R0805")
      (libsource (lib "eagle-import") (part "R-EU_R0805"))
    )
    (comp (ref "R15")
      (value "1600")
      (footprint "eagle-import:R0805")
      (libsource (lib "eagle-import") (part "R-EU_R0805"))
    )
    (comp (ref "R16")
      (value "1600")
      (footprint "eagle-import:R0805")
      (libsource (lib "eagle-import") (part "R-EU_R0805"))
    )
    (comp (ref "R17")
      (value "1600")
      (footprint "eagle-import:R0805")
      (libsource (lib "eagle-import") (part "R-EU_R0805"))
    )
    (comp (ref "R18")
      (value "1600")
      (footprint "eagle-import:R0805")
      (libsource (lib "eagle-import") (part "R-EU_R0805"))
    )
    (comp (ref "R19")
      (value "1600")
      (footprint "eagle-import:R0805")
      (libsource (lib "eagle-import") (part "R-EU_R0805"))
    )
    (comp (ref "R20")
      (value "1600")
      (footprint "eagle-import:R0805")
      (libsource (lib "eagle-import") (part "R-EU_R0805"))
    )
    (comp (ref "R21")
      (value "1600")
      (footprint "eagle-import:R0805")
      (libsource (lib "eagle-import") (part "R-EU_R0805"))
    )
    (comp (ref "R22")
      (value "1600")
      (footprint "eagle-import:R0805")
      (libsource (lib "eagle-import") (part "R-EU_R0805"))
    )
    (comp (ref "R23")
      (value "1600")
      (footprint "eagle-import:R0805")
      (libsource (lib "eagle-import") (part "R-EU_R0805"))
    )
    (comp (ref "R24")
      (value "1600")
      (footprint "eagle-import:R0805")
      (libsource (lib "eagle-import") (part "R-EU_R0805"))
    )
    (comp (ref "R25")
      (value "1600")
      (footprint "eagle-import:R0805")
      (libsource (lib "eagle-import") (part "R-EU_R0805"))
    )
    (comp (ref "R26")
      (value "1600")
      (footprint "eagle-import:R0805")
      (libsource (lib "eagle-import") (part "R-EU_R0805"))
    )
    (comp (ref "R27")
      (value "1600")
      (footprint "eagle-import:R0805")
      (libsource (lib "eagle-import") (part "R-EU_R0805"))
    )
    (comp (ref "R28")
      (value "1600")
      (footprint "eagle-import:R0805")
      (libsource (lib "eagle-import") (part "R-EU_R0805"))
    )
    (comp (ref "R29")
      (value "1600")
      (footprint "eagle-import:R0805")
      (libsource (lib "eagle-import") (part "R-EU_R0805"))
    )
    (comp (ref "R30")
      (value "1600")
      (footprint "eagle-import:R0805")
      (libsource (lib "eagle-import") (part "R-EU_R0805"))
    )
    (comp (ref "R31")
      (value "1600")
      (footprint "eagle-import:R0805")
      (libsource (lib "eagle-import") (part "R-EU_R0805"))
    )
    (comp (ref "R32")
      (value "1600")
      (footprint "eagle-import:R0805")
      (libsource (lib "eagle-import") (part "R-EU_R0805"))
    )
    (comp (ref "R33")
      (value "560")
      (footprint "eagle-import:R0805")
      (libsource (lib "eagle-import") (part "R-EU_R0805"))
    )
    (comp (ref "R34")
      (value "560")
      (footprint "eagle-import:R0805")
      (libsource (lib "eagle-import") (part "R-EU_R0805"))
    )
    (comp (ref "R35")
      (value "560")
      (footprint "eagle-import:R0805")
      (libsource (lib "eagle-import") (part "R-EU_R0805"))
    )
    (comp (ref "R36")
      (value "560")
      (footprint "eagle-import:R0805")
      (libsource (lib "eagle-import") (part "R-EU_R0805"))
    )
    (comp (ref "R37")
      (value "560")
      (footprint "eagle-import:R0805")
      (libsource (lib "eagle-import") (part "R-EU_R0805"))
    )
    (comp (ref "R38")
      (value "560")
      (footprint "eagle-import:R0805")
      (libsource (lib "eagle-import") (part "R-EU_R0805"))
    )
    (comp (ref "R40")
      (value "560")
      (footprint "eagle-import:R0805")
      (libsource (lib "eagle-import") (part "R-EU_R0805"))
    )
    (comp (ref "R41")
      (value "PULL DOWN")
      (footprint "eagle-import:R0805")
      (libsource (lib "eagle-import") (part "R-EU_R0805"))
    )
    (comp (ref "R42")
      (value "560")
      (footprint "eagle-import:R0805")
      (libsource (lib "eagle-import") (part "R-EU_R0805"))
    )
    (comp (ref "R43")
      (value "560")
      (footprint "eagle-import:R0805")
      (libsource (lib "eagle-import") (part "R-EU_R0805"))
    )
    (comp (ref "R44")
      (value "560")
      (footprint "eagle-import:R0805")
      (libsource (lib "eagle-import") (part "R-EU_R0805"))
    )
    (comp (ref "R45")
      (value "560")
      (footprint "eagle-import:R0805")
      (libsource (lib "eagle-import") (part "R-EU_R0805"))
    )
    (comp (ref "R46")
      (value "560")
      (footprint "eagle-import:R0805")
      (libsource (lib "eagle-import") (part "R-EU_R0805"))
    )
    (comp (ref "R47")
      (value "560")
      (footprint "eagle-import:R0805")
      (libsource (lib "eagle-import") (part "R-EU_R0805"))
    )
    (comp (ref "R48")
      (value "560")
      (footprint "eagle-import:R0805")
      (libsource (lib "eagle-import") (part "R-EU_R0805"))
    )
    (comp (ref "R49")
      (value "560")
      (footprint "eagle-import:R0805")
      (libsource (lib "eagle-import") (part "R-EU_R0805"))
    )
    (comp (ref "R50")
      (value "560")
      (footprint "eagle-import:R0805")
      (libsource (lib "eagle-import") (part "R-EU_R0805"))
    )
    (comp (ref "R51")
      (value "560")
      (footprint "eagle-import:R0805")
      (libsource (lib "eagle-import") (part "R-EU_R0805"))
    )
    (comp (ref "R52")
      (value "560")
      (footprint "eagle-import:R0805")
      (libsource (lib "eagle-import") (part "R-EU_R0805"))
    )
    (comp (ref "R53")
      (value "560")
      (footprint "eagle-import:R0805")
      (libsource (lib "eagle-import") (part "R-EU_R0805"))
    )
    (comp (ref "R54")
      (value "560")
      (footprint "eagle-import:R0805")
      (libsource (lib "eagle-import") (part "R-EU_R0805"))
    )
    (comp (ref "R55")
      (value "560")
      (footprint "eagle-import:R0805")
      (libsource (lib "eagle-import") (part "R-EU_R0805"))
    )
    (comp (ref "R56")
      (value "560")
      (footprint "eagle-import:R0805")
      (libsource (lib "eagle-import") (part "R-EU_R0805"))
    )
    (comp (ref "R57")
      (value "560")
      (footprint "eagle-import:R0805")
      (libsource (lib "eagle-import") (part "R-EU_R0805"))
    )
    (comp (ref "SV_ALU_1")
      (value "MA18-2")
      (footprint "eagle-import:MA18-2")
      (libsource (lib "eagle-import") (part "MA18-2"))
    )
    (comp (ref "SV_ALU_2")
      (value "MA18-2")
      (footprint "eagle-import:MA18-2")
      (libsource (lib "eagle-import") (part "MA18-2"))
    )
    (comp (ref "SV_ALU_SUP1")
      (value "MA03-2")
      (footprint "eagle-import:MA03-2")
      (libsource (lib "eagle-import") (part "MA03-2"))
    )
    (comp (ref "SV_ALU_SUP2")
      (value "MA03-2")
      (footprint "eagle-import:MA03-2")
      (libsource (lib "eagle-import") (part "MA03-2"))
    )
    (comp (ref "SV_ALU_SUP3")
      (value "MA03-2")
      (footprint "eagle-import:MA03-2")
      (libsource (lib "eagle-import") (part "MA03-2"))
    )
    (comp (ref "SV_ALU_SUP4")
      (value "MA03-2")
      (footprint "eagle-import:MA03-2")
      (libsource (lib "eagle-import") (part "MA03-2"))
    )
    (comp (ref "SV_ALU_SUP5")
      (value "MA03-2")
      (footprint "eagle-import:MA03-2")
      (libsource (lib "eagle-import") (part "MA03-2"))
    )
    (comp (ref "SV_ALU_SUP6")
      (value "MA03-2")
      (footprint "eagle-import:MA03-2")
      (libsource (lib "eagle-import") (part "MA03-2"))
    )
  )
  (nets
    (net (code "1") (name "/ADC") (class "Default")
      (node (ref "IC3") (pin "2") (pinfunction "1_2") (pintype "output"))
      (node (ref "IC6") (pin "2") (pinfunction "I1_2") (pintype "input"))
      (node (ref "IC9") (pin "1") (pinfunction "I0_1") (pintype "input"))
      (node (ref "R43") (pin "1") (pinfunction "1_1") (pintype "passive"))
    )
    (net (code "2") (name "/ADD") (class "Default")
      (node (ref "IC3") (pin "1") (pinfunction "0_1") (pintype "output"))
      (node (ref "IC6") (pin "1") (pinfunction "I0_1") (pintype "input"))
      (node (ref "R42") (pin "1") (pinfunction "1_1") (pintype "passive"))
    )
    (net (code "3") (name "/AND") (class "Default")
      (node (ref "IC14") (pin "19") (pinfunction "G_19") (pintype "input"))
      (node (ref "IC3") (pin "7") (pinfunction "6_7") (pintype "output"))
      (node (ref "R48") (pin "1") (pinfunction "1_1") (pintype "passive"))
    )
    (net (code "4") (name "/ARS") (class "Default")
      (node (ref "IC23") (pin "19") (pinfunction "G_19") (pintype "input"))
      (node (ref "IC3") (pin "15") (pinfunction "13_15") (pintype "output"))
      (node (ref "R55") (pin "1") (pinfunction "1_1") (pintype "passive"))
    )
    (net (code "5") (name "/BUS_~{CLK}") (class "Default")
      (node (ref "SV_ALU_1") (pin "32") (pinfunction "32_32") (pintype "passive"))
    )
    (net (code "6") (name "/BUS_~{RESET}") (class "Default")
      (node (ref "IC36") (pin "1") (pinfunction "CLR_1") (pintype "input"))
      (node (ref "SV_ALU_1") (pin "28") (pinfunction "28_28") (pintype "passive"))
    )
    (net (code "7") (name "/DEC") (class "Default")
      (node (ref "IC3") (pin "6") (pinfunction "5_6") (pintype "output"))
      (node (ref "IC6") (pin "10") (pinfunction "I1_10") (pintype "input"))
      (node (ref "IC8") (pin "5") (pinfunction "I_5") (pintype "input"))
      (node (ref "R47") (pin "1") (pinfunction "1_1") (pintype "passive"))
    )
    (net (code "8") (name "/INC") (class "Default")
      (node (ref "IC3") (pin "5") (pinfunction "4_5") (pintype "output"))
      (node (ref "IC6") (pin "9") (pinfunction "I0_9") (pintype "input"))
      (node (ref "IC9") (pin "5") (pinfunction "I1_5") (pintype "input"))
      (node (ref "R46") (pin "1") (pinfunction "1_1") (pintype "passive"))
    )
    (net (code "9") (name "/LRS") (class "Default")
      (node (ref "IC22") (pin "19") (pinfunction "G_19") (pintype "input"))
      (node (ref "IC3") (pin "14") (pinfunction "12_14") (pintype "output"))
      (node (ref "R54") (pin "1") (pinfunction "1_1") (pintype "passive"))
    )
    (net (code "10") (name "/NEG") (class "Default")
      (node (ref "IC3") (pin "11") (pinfunction "10_11") (pintype "output"))
      (node (ref "IC6") (pin "13") (pinfunction "I1_13") (pintype "input"))
      (node (ref "IC8") (pin "11") (pinfunction "I_11") (pintype "input"))
      (node (ref "IC9") (pin "4") (pinfunction "I0_4") (pintype "input"))
      (node (ref "R52") (pin "1") (pinfunction "1_1") (pintype "passive"))
    )
    (net (code "11") (name "/NOT") (class "Default")
      (node (ref "IC3") (pin "10") (pinfunction "9_10") (pintype "output"))
      (node (ref "IC6") (pin "12") (pinfunction "I0_12") (pintype "input"))
      (node (ref "IC8") (pin "9") (pinfunction "I_9") (pintype "input"))
      (node (ref "R51") (pin "1") (pinfunction "1_1") (pintype "passive"))
    )
    (net (code "12") (name "/OR") (class "Default")
      (node (ref "IC15") (pin "19") (pinfunction "G_19") (pintype "input"))
      (node (ref "IC3") (pin "8") (pinfunction "7_8") (pintype "output"))
      (node (ref "R49") (pin "1") (pinfunction "1_1") (pintype "passive"))
    )
    (net (code "13") (name "/ROL") (class "Default")
      (node (ref "IC24") (pin "19") (pinfunction "G_19") (pintype "input"))
      (node (ref "IC3") (pin "16") (pinfunction "14_16") (pintype "output"))
      (node (ref "R56") (pin "1") (pinfunction "1_1") (pintype "passive"))
    )
    (net (code "14") (name "/ROR") (class "Default")
      (node (ref "IC25") (pin "19") (pinfunction "G_19") (pintype "input"))
      (node (ref "IC3") (pin "17") (pinfunction "15_17") (pintype "output"))
      (node (ref "R57") (pin "1") (pinfunction "1_1") (pintype "passive"))
    )
    (net (code "15") (name "/SBC") (class "Default")
      (node (ref "IC3") (pin "4") (pinfunction "3_4") (pintype "output"))
      (node (ref "IC6") (pin "5") (pinfunction "I1_5") (pintype "input"))
      (node (ref "IC8") (pin "3") (pinfunction "I_3") (pintype "input"))
      (node (ref "IC9") (pin "2") (pinfunction "I1_2") (pintype "input"))
      (node (ref "R45") (pin "1") (pinfunction "1_1") (pintype "passive"))
    )
    (net (code "16") (name "/SHL") (class "Default")
      (node (ref "IC21") (pin "19") (pinfunction "G_19") (pintype "input"))
      (node (ref "IC3") (pin "13") (pinfunction "11_13") (pintype "output"))
      (node (ref "R53") (pin "1") (pinfunction "1_1") (pintype "passive"))
    )
    (net (code "17") (name "/SUB") (class "Default")
      (node (ref "IC3") (pin "3") (pinfunction "2_3") (pintype "output"))
      (node (ref "IC6") (pin "4") (pinfunction "I0_4") (pintype "input"))
      (node (ref "IC8") (pin "1") (pinfunction "I_1") (pintype "input"))
      (node (ref "R44") (pin "1") (pinfunction "1_1") (pintype "passive"))
    )
    (net (code "18") (name "/XOR") (class "Default")
      (node (ref "IC16") (pin "19") (pinfunction "G_19") (pintype "input"))
      (node (ref "IC3") (pin "9") (pinfunction "8_9") (pintype "output"))
      (node (ref "R50") (pin "1") (pinfunction "1_1") (pintype "passive"))
    )
    (net (code "19") (name "/~{CTRL_ALU_ASSERT}") (class "Default")
      (node (ref "D40") (pin "1") (pinfunction "K2_1") (pintype "passive"))
      (node (ref "IC38") (pin "19") (pinfunction "G_19") (pintype "input"))
      (node (ref "SV_ALU_2") (pin "32") (pinfunction "32_32") (pintype "passive"))
    )
    (net (code "20") (name "ALU_CARRY_FLAG") (class "Default")
      (node (ref "IC2") (pin "9") (pinfunction "C4_9") (pintype "output"))
      (node (ref "SV_ALU_2") (pin "33") (pinfunction "33_33") (pintype "passive"))
    )
    (net (code "21") (name "ALU_SIGN_FLAG") (class "Default")
      (node (ref "D1") (pin "A") (pinfunction "A_A") (pintype "passive"))
      (node (ref "IC12") (pin "2") (pinfunction "A1_2") (pintype "bidirectional"))
      (node (ref "IC14") (pin "2") (pinfunction "A1_2") (pintype "bidirectional"))
      (node (ref "IC15") (pin "2") (pinfunction "A1_2") (pintype "bidirectional"))
      (node (ref "IC16") (pin "2") (pinfunction "A1_2") (pintype "bidirectional"))
      (node (ref "IC21") (pin "2") (pinfunction "A1_2") (pintype "bidirectional"))
      (node (ref "IC22") (pin "2") (pinfunction "A1_2") (pintype "bidirectional"))
      (node (ref "IC23") (pin "2") (pinfunction "A1_2") (pintype "bidirectional"))
      (node (ref "IC24") (pin "2") (pinfunction "A1_2") (pintype "bidirectional"))
      (node (ref "IC25") (pin "2") (pinfunction "A1_2") (pintype "bidirectional"))
      (node (ref "IC36") (pin "3") (pinfunction "D1_3") (pintype "input"))
      (node (ref "IC37") (pin "2") (pinfunction "I0_2") (pintype "input"))
      (node (ref "SV_ALU_2") (pin "29") (pinfunction "29_29") (pintype "passive"))
    )
    (net (code "22") (name "ALU_ZERO_FLAG") (class "Default")
      (node (ref "IC39") (pin "8") (pinfunction "O_8") (pintype "output"))
      (node (ref "SV_ALU_2") (pin "31") (pinfunction "31_31") (pintype "passive"))
    )
    (net (code "23") (name "BUS_CARRY_FLAG") (class "Default")
      (node (ref "IC7") (pin "12") (pinfunction "I0_12") (pintype "input"))
      (node (ref "SV_ALU_2") (pin "27") (pinfunction "27_27") (pintype "passive"))
    )
    (net (code "24") (name "BUS_CLK") (class "Default")
      (node (ref "D37") (pin "2") (pinfunction "A2_2") (pintype "passive"))
      (node (ref "IC36") (pin "11") (pinfunction "CLK_11") (pintype "input"))
      (node (ref "SV_ALU_1") (pin "34") (pinfunction "34_34") (pintype "passive"))
    )
    (net (code "25") (name "BUS_MAIN_BUS_0") (class "Default")
      (node (ref "IC38") (pin "18") (pinfunction "B1_18") (pintype "bidirectional"))
      (node (ref "SV_ALU_2") (pin "17") (pinfunction "17_17") (pintype "passive"))
    )
    (net (code "26") (name "BUS_MAIN_BUS_1") (class "Default")
      (node (ref "IC38") (pin "17") (pinfunction "B2_17") (pintype "bidirectional"))
      (node (ref "SV_ALU_2") (pin "15") (pinfunction "15_15") (pintype "passive"))
    )
    (net (code "27") (name "BUS_MAIN_BUS_2") (class "Default")
      (node (ref "IC38") (pin "16") (pinfunction "B3_16") (pintype "bidirectional"))
      (node (ref "SV_ALU_2") (pin "13") (pinfunction "13_13") (pintype "passive"))
    )
    (net (code "28") (name "BUS_MAIN_BUS_3") (class "Default")
      (node (ref "IC38") (pin "15") (pinfunction "B4_15") (pintype "bidirectional"))
      (node (ref "SV_ALU_2") (pin "11") (pinfunction "11_11") (pintype "passive"))
    )
    (net (code "29") (name "BUS_MAIN_BUS_4") (class "Default")
      (node (ref "IC38") (pin "14") (pinfunction "B5_14") (pintype "bidirectional"))
      (node (ref "SV_ALU_2") (pin "9") (pinfunction "9_9") (pintype "passive"))
    )
    (net (code "30") (name "BUS_MAIN_BUS_5") (class "Default")
      (node (ref "IC38") (pin "13") (pinfunction "B6_13") (pintype "bidirectional"))
      (node (ref "SV_ALU_2") (pin "7") (pinfunction "7_7") (pintype "passive"))
    )
    (net (code "31") (name "BUS_MAIN_BUS_6") (class "Default")
      (node (ref "IC38") (pin "12") (pinfunction "B7_12") (pintype "bidirectional"))
      (node (ref "SV_ALU_2") (pin "5") (pinfunction "5_5") (pintype "passive"))
    )
    (net (code "32") (name "BUS_MAIN_BUS_7") (class "Default")
      (node (ref "IC38") (pin "11") (pinfunction "B8_11") (pintype "bidirectional"))
      (node (ref "SV_ALU_2") (pin "3") (pinfunction "3_3") (pintype "passive"))
    )
    (net (code "33") (name "BUS_RESET") (class "Default")
      (node (ref "D38") (pin "2") (pinfunction "A2_2") (pintype "passive"))
      (node (ref "SV_ALU_1") (pin "30") (pinfunction "30_30") (pintype "passive"))
    )
    (net (code "34") (name "BUS_SIGN_FLAG") (class "Default")
      (node (ref "SV_ALU_2") (pin "23") (pinfunction "23_23") (pintype "passive"))
    )
    (net (code "35") (name "BUS_ZERO_FLAG") (class "Default")
      (node (ref "SV_ALU_2") (pin "25") (pinfunction "25_25") (pintype "passive"))
    )
    (net (code "36") (name "CTRL25_ALU_OP_1") (class "Default")
      (node (ref "D36") (pin "1") (pinfunction "K2_1") (pintype "passive"))
      (node (ref "IC3") (pin "23") (pinfunction "A_23") (pintype "input"))
      (node (ref "SV_ALU_2") (pin "24") (pinfunction "24_24") (pintype "passive"))
    )
    (net (code "37") (name "CTRL26_ALU_OP_2") (class "Default")
      (node (ref "D35") (pin "1") (pinfunction "K2_1") (pintype "passive"))
      (node (ref "IC3") (pin "22") (pinfunction "B_22") (pintype "input"))
      (node (ref "SV_ALU_2") (pin "26") (pinfunction "26_26") (pintype "passive"))
    )
    (net (code "38") (name "CTRL27_ALU_OP_3") (class "Default")
      (node (ref "D34") (pin "1") (pinfunction "K2_1") (pintype "passive"))
      (node (ref "IC3") (pin "21") (pinfunction "C_21") (pintype "input"))
      (node (ref "SV_ALU_2") (pin "28") (pinfunction "28_28") (pintype "passive"))
    )
    (net (code "39") (name "CTRL28_ALU_OP_4") (class "Default")
      (node (ref "D33") (pin "1") (pinfunction "K2_1") (pintype "passive"))
      (node (ref "IC3") (pin "20") (pinfunction "D_20") (pintype "input"))
      (node (ref "SV_ALU_2") (pin "30") (pinfunction "30_30") (pintype "passive"))
    )
    (net (code "40") (name "GND") (class "Default")
      (node (ref "C1") (pin "2") (pinfunction "2_2") (pintype "passive"))
      (node (ref "C10") (pin "2") (pinfunction "2_2") (pintype "passive"))
      (node (ref "C11") (pin "2") (pinfunction "2_2") (pintype "passive"))
      (node (ref "C12") (pin "2") (pinfunction "2_2") (pintype "passive"))
      (node (ref "C13") (pin "2") (pinfunction "2_2") (pintype "passive"))
      (node (ref "C14") (pin "2") (pinfunction "2_2") (pintype "passive"))
      (node (ref "C15") (pin "2") (pinfunction "2_2") (pintype "passive"))
      (node (ref "C16") (pin "2") (pinfunction "2_2") (pintype "passive"))
      (node (ref "C17") (pin "2") (pinfunction "2_2") (pintype "passive"))
      (node (ref "C18") (pin "2") (pinfunction "2_2") (pintype "passive"))
      (node (ref "C19") (pin "2") (pinfunction "2_2") (pintype "passive"))
      (node (ref "C2") (pin "2") (pinfunction "2_2") (pintype "passive"))
      (node (ref "C20") (pin "2") (pinfunction "2_2") (pintype "passive"))
      (node (ref "C21") (pin "2") (pinfunction "2_2") (pintype "passive"))
      (node (ref "C22") (pin "2") (pinfunction "2_2") (pintype "passive"))
      (node (ref "C23") (pin "2") (pinfunction "2_2") (pintype "passive"))
      (node (ref "C24") (pin "2") (pinfunction "2_2") (pintype "passive"))
      (node (ref "C25") (pin "2") (pinfunction "2_2") (pintype "passive"))
      (node (ref "C26") (pin "2") (pinfunction "2_2") (pintype "passive"))
      (node (ref "C27") (pin "2") (pinfunction "2_2") (pintype "passive"))
      (node (ref "C28") (pin "2") (pinfunction "2_2") (pintype "passive"))
      (node (ref "C29") (pin "2") (pinfunction "2_2") (pintype "passive"))
      (node (ref "C3") (pin "2") (pinfunction "2_2") (pintype "passive"))
      (node (ref "C30") (pin "2") (pinfunction "2_2") (pintype "passive"))
      (node (ref "C31") (pin "2") (pinfunction "2_2") (pintype "passive"))
      (node (ref "C32") (pin "2") (pinfunction "2_2") (pintype "passive"))
      (node (ref "C33") (pin "2") (pinfunction "2_2") (pintype "passive"))
      (node (ref "C4") (pin "2") (pinfunction "2_2") (pintype "passive"))
      (node (ref "C5") (pin "2") (pinfunction "2_2") (pintype "passive"))
      (node (ref "C6") (pin "2") (pinfunction "2_2") (pintype "passive"))
      (node (ref "C7") (pin "2") (pinfunction "2_2") (pintype "passive"))
      (node (ref "C8") (pin "2") (pinfunction "2_2") (pintype "passive"))
      (node (ref "C9") (pin "2") (pinfunction "2_2") (pintype "passive"))
      (node (ref "IC1") (pin "8") (pinfunction "GND_8") (pintype "power_in"))
      (node (ref "IC10") (pin "7") (pinfunction "GND_7") (pintype "power_in"))
      (node (ref "IC11") (pin "7") (pinfunction "GND_7") (pintype "power_in"))
      (node (ref "IC12") (pin "1") (pinfunction "DIR_1") (pintype "input"))
      (node (ref "IC12") (pin "10") (pinfunction "GND_10") (pintype "power_in"))
      (node (ref "IC13") (pin "7") (pinfunction "GND_7") (pintype "power_in"))
      (node (ref "IC14") (pin "1") (pinfunction "DIR_1") (pintype "input"))
      (node (ref "IC14") (pin "10") (pinfunction "GND_10") (pintype "power_in"))
      (node (ref "IC15") (pin "1") (pinfunction "DIR_1") (pintype "input"))
      (node (ref "IC15") (pin "10") (pinfunction "GND_10") (pintype "power_in"))
      (node (ref "IC16") (pin "1") (pinfunction "DIR_1") (pintype "input"))
      (node (ref "IC16") (pin "10") (pinfunction "GND_10") (pintype "power_in"))
      (node (ref "IC17") (pin "7") (pinfunction "GND_7") (pintype "power_in"))
      (node (ref "IC18") (pin "7") (pinfunction "GND_7") (pintype "power_in"))
      (node (ref "IC19") (pin "7") (pinfunction "GND_7") (pintype "power_in"))
      (node (ref "IC2") (pin "8") (pinfunction "GND_8") (pintype "power_in"))
      (node (ref "IC20") (pin "7") (pinfunction "GND_7") (pintype "power_in"))
      (node (ref "IC21") (pin "1") (pinfunction "DIR_1") (pintype "input"))
      (node (ref "IC21") (pin "10") (pinfunction "GND_10") (pintype "power_in"))
      (node (ref "IC22") (pin "1") (pinfunction "DIR_1") (pintype "input"))
      (node (ref "IC22") (pin "10") (pinfunction "GND_10") (pintype "power_in"))
      (node (ref "IC23") (pin "1") (pinfunction "DIR_1") (pintype "input"))
      (node (ref "IC23") (pin "10") (pinfunction "GND_10") (pintype "power_in"))
      (node (ref "IC24") (pin "1") (pinfunction "DIR_1") (pintype "input"))
      (node (ref "IC24") (pin "10") (pinfunction "GND_10") (pintype "power_in"))
      (node (ref "IC25") (pin "1") (pinfunction "DIR_1") (pintype "input"))
      (node (ref "IC25") (pin "10") (pinfunction "GND_10") (pintype "power_in"))
      (node (ref "IC3") (pin "12") (pinfunction "GND_12") (pintype "power_in"))
      (node (ref "IC3") (pin "18") (pinfunction "G1_18") (pintype "input"))
      (node (ref "IC3") (pin "19") (pinfunction "G2_19") (pintype "input"))
      (node (ref "IC36") (pin "10") (pinfunction "GND_10") (pintype "power_in"))
      (node (ref "IC37") (pin "7") (pinfunction "GND_7") (pintype "power_in"))
      (node (ref "IC38") (pin "10") (pinfunction "GND_10") (pintype "power_in"))
      (node (ref "IC39") (pin "7") (pinfunction "GND_7") (pintype "power_in"))
      (node (ref "IC4") (pin "7") (pinfunction "GND_7") (pintype "power_in"))
      (node (ref "IC5") (pin "7") (pinfunction "GND_7") (pintype "power_in"))
      (node (ref "IC6") (pin "7") (pinfunction "GND_7") (pintype "power_in"))
      (node (ref "IC7") (pin "7") (pinfunction "GND_7") (pintype "power_in"))
      (node (ref "IC8") (pin "7") (pinfunction "GND_7") (pintype "power_in"))
      (node (ref "IC9") (pin "7") (pinfunction "GND_7") (pintype "power_in"))
      (node (ref "R1") (pin "2") (pinfunction "2_2") (pintype "passive"))
      (node (ref "R10") (pin "2") (pinfunction "2_2") (pintype "passive"))
      (node (ref "R11") (pin "2") (pinfunction "2_2") (pintype "passive"))
      (node (ref "R12") (pin "2") (pinfunction "2_2") (pintype "passive"))
      (node (ref "R13") (pin "2") (pinfunction "2_2") (pintype "passive"))
      (node (ref "R14") (pin "2") (pinfunction "2_2") (pintype "passive"))
      (node (ref "R15") (pin "2") (pinfunction "2_2") (pintype "passive"))
      (node (ref "R16") (pin "2") (pinfunction "2_2") (pintype "passive"))
      (node (ref "R17") (pin "2") (pinfunction "2_2") (pintype "passive"))
      (node (ref "R18") (pin "2") (pinfunction "2_2") (pintype "passive"))
      (node (ref "R19") (pin "2") (pinfunction "2_2") (pintype "passive"))
      (node (ref "R2") (pin "2") (pinfunction "2_2") (pintype "passive"))
      (node (ref "R20") (pin "2") (pinfunction "2_2") (pintype "passive"))
      (node (ref "R21") (pin "2") (pinfunction "2_2") (pintype "passive"))
      (node (ref "R22") (pin "2") (pinfunction "2_2") (pintype "passive"))
      (node (ref "R23") (pin "2") (pinfunction "2_2") (pintype "passive"))
      (node (ref "R24") (pin "2") (pinfunction "2_2") (pintype "passive"))
      (node (ref "R25") (pin "2") (pinfunction "2_2") (pintype "passive"))
      (node (ref "R26") (pin "2") (pinfunction "2_2") (pintype "passive"))
      (node (ref "R27") (pin "2") (pinfunction "2_2") (pintype "passive"))
      (node (ref "R28") (pin "2") (pinfunction "2_2") (pintype "passive"))
      (node (ref "R29") (pin "2") (pinfunction "2_2") (pintype "passive"))
      (node (ref "R3") (pin "2") (pinfunction "2_2") (pintype "passive"))
      (node (ref "R30") (pin "2") (pinfunction "2_2") (pintype "passive"))
      (node (ref "R31") (pin "2") (pinfunction "2_2") (pintype "passive"))
      (node (ref "R32") (pin "2") (pinfunction "2_2") (pintype "passive"))
      (node (ref "R33") (pin "2") (pinfunction "2_2") (pintype "passive"))
      (node (ref "R34") (pin "2") (pinfunction "2_2") (pintype "passive"))
      (node (ref "R35") (pin "2") (pinfunction "2_2") (pintype "passive"))
      (node (ref "R36") (pin "2") (pinfunction "2_2") (pintype "passive"))
      (node (ref "R37") (pin "2") (pinfunction "2_2") (pintype "passive"))
      (node (ref "R38") (pin "2") (pinfunction "2_2") (pintype "passive"))
      (node (ref "R4") (pin "2") (pinfunction "2_2") (pintype "passive"))
      (node (ref "R41") (pin "2") (pinfunction "2_2") (pintype "passive"))
      (node (ref "R5") (pin "2") (pinfunction "2_2") (pintype "passive"))
      (node (ref "R6") (pin "2") (pinfunction "2_2") (pintype "passive"))
      (node (ref "R7") (pin "2") (pinfunction "2_2") (pintype "passive"))
      (node (ref "R8") (pin "2") (pinfunction "2_2") (pintype "passive"))
      (node (ref "R9") (pin "2") (pinfunction "2_2") (pintype "passive"))
      (node (ref "SV_ALU_1") (pin "2") (pinfunction "2_2") (pintype "passive"))
      (node (ref "SV_ALU_1") (pin "35") (pinfunction "35_35") (pintype "passive"))
      (node (ref "SV_ALU_2") (pin "2") (pinfunction "2_2") (pintype "passive"))
      (node (ref "SV_ALU_2") (pin "35") (pinfunction "35_35") (pintype "passive"))
      (node (ref "SV_ALU_SUP1") (pin "2") (pinfunction "2_2") (pintype "passive"))
      (node (ref "SV_ALU_SUP1") (pin "4") (pinfunction "4_4") (pintype "passive"))
      (node (ref "SV_ALU_SUP1") (pin "6") (pinfunction "6_6") (pintype "passive"))
      (node (ref "SV_ALU_SUP2") (pin "2") (pinfunction "2_2") (pintype "passive"))
      (node (ref "SV_ALU_SUP2") (pin "4") (pinfunction "4_4") (pintype "passive"))
      (node (ref "SV_ALU_SUP2") (pin "6") (pinfunction "6_6") (pintype "passive"))
      (node (ref "SV_ALU_SUP3") (pin "2") (pinfunction "2_2") (pintype "passive"))
      (node (ref "SV_ALU_SUP3") (pin "4") (pinfunction "4_4") (pintype "passive"))
      (node (ref "SV_ALU_SUP3") (pin "6") (pinfunction "6_6") (pintype "passive"))
      (node (ref "SV_ALU_SUP4") (pin "2") (pinfunction "2_2") (pintype "passive"))
      (node (ref "SV_ALU_SUP4") (pin "4") (pinfunction "4_4") (pintype "passive"))
      (node (ref "SV_ALU_SUP4") (pin "6") (pinfunction "6_6") (pintype "passive"))
      (node (ref "SV_ALU_SUP5") (pin "2") (pinfunction "2_2") (pintype "passive"))
      (node (ref "SV_ALU_SUP5") (pin "4") (pinfunction "4_4") (pintype "passive"))
      (node (ref "SV_ALU_SUP5") (pin "6") (pinfunction "6_6") (pintype "passive"))
      (node (ref "SV_ALU_SUP6") (pin "2") (pinfunction "2_2") (pintype "passive"))
      (node (ref "SV_ALU_SUP6") (pin "4") (pinfunction "4_4") (pintype "passive"))
      (node (ref "SV_ALU_SUP6") (pin "6") (pinfunction "6_6") (pintype "passive"))
    )
    (net (code "41") (name "Net-(D1-PadC)") (class "Default")
      (node (ref "D1") (pin "C") (pinfunction "C_C") (pintype "passive"))
      (node (ref "R1") (pin "1") (pinfunction "1_1") (pintype "passive"))
    )
    (net (code "42") (name "Net-(D2-PadC)") (class "Default")
      (node (ref "D2") (pin "C") (pinfunction "C_C") (pintype "passive"))
      (node (ref "R2") (pin "1") (pinfunction "1_1") (pintype "passive"))
    )
    (net (code "43") (name "Net-(D3-PadC)") (class "Default")
      (node (ref "D3") (pin "C") (pinfunction "C_C") (pintype "passive"))
      (node (ref "R3") (pin "1") (pinfunction "1_1") (pintype "passive"))
    )
    (net (code "44") (name "Net-(D4-PadC)") (class "Default")
      (node (ref "D4") (pin "C") (pinfunction "C_C") (pintype "passive"))
      (node (ref "R4") (pin "1") (pinfunction "1_1") (pintype "passive"))
    )
    (net (code "45") (name "Net-(D5-PadC)") (class "Default")
      (node (ref "D5") (pin "C") (pinfunction "C_C") (pintype "passive"))
      (node (ref "R5") (pin "1") (pinfunction "1_1") (pintype "passive"))
    )
    (net (code "46") (name "Net-(D6-PadC)") (class "Default")
      (node (ref "D6") (pin "C") (pinfunction "C_C") (pintype "passive"))
      (node (ref "R6") (pin "1") (pinfunction "1_1") (pintype "passive"))
    )
    (net (code "47") (name "Net-(D7-PadC)") (class "Default")
      (node (ref "D7") (pin "C") (pinfunction "C_C") (pintype "passive"))
      (node (ref "R7") (pin "1") (pinfunction "1_1") (pintype "passive"))
    )
    (net (code "48") (name "Net-(D8-PadC)") (class "Default")
      (node (ref "D8") (pin "C") (pinfunction "C_C") (pintype "passive"))
      (node (ref "R8") (pin "1") (pinfunction "1_1") (pintype "passive"))
    )
    (net (code "49") (name "Net-(D9-PadC)") (class "Default")
      (node (ref "D9") (pin "C") (pinfunction "C_C") (pintype "passive"))
      (node (ref "R9") (pin "1") (pinfunction "1_1") (pintype "passive"))
    )
    (net (code "50") (name "Net-(D10-PadC)") (class "Default")
      (node (ref "D10") (pin "C") (pinfunction "C_C") (pintype "passive"))
      (node (ref "R10") (pin "1") (pinfunction "1_1") (pintype "passive"))
    )
    (net (code "51") (name "Net-(D11-PadC)") (class "Default")
      (node (ref "D11") (pin "C") (pinfunction "C_C") (pintype "passive"))
      (node (ref "R11") (pin "1") (pinfunction "1_1") (pintype "passive"))
    )
    (net (code "52") (name "Net-(D12-PadC)") (class "Default")
      (node (ref "D12") (pin "C") (pinfunction "C_C") (pintype "passive"))
      (node (ref "R12") (pin "1") (pinfunction "1_1") (pintype "passive"))
    )
    (net (code "53") (name "Net-(D13-PadC)") (class "Default")
      (node (ref "D13") (pin "C") (pinfunction "C_C") (pintype "passive"))
      (node (ref "R13") (pin "1") (pinfunction "1_1") (pintype "passive"))
    )
    (net (code "54") (name "Net-(D14-PadC)") (class "Default")
      (node (ref "D14") (pin "C") (pinfunction "C_C") (pintype "passive"))
      (node (ref "R14") (pin "1") (pinfunction "1_1") (pintype "passive"))
    )
    (net (code "55") (name "Net-(D15-PadC)") (class "Default")
      (node (ref "D15") (pin "C") (pinfunction "C_C") (pintype "passive"))
      (node (ref "R15") (pin "1") (pinfunction "1_1") (pintype "passive"))
    )
    (net (code "56") (name "Net-(D16-PadC)") (class "Default")
      (node (ref "D16") (pin "C") (pinfunction "C_C") (pintype "passive"))
      (node (ref "R16") (pin "1") (pinfunction "1_1") (pintype "passive"))
    )
    (net (code "57") (name "Net-(D17-PadC)") (class "Default")
      (node (ref "D17") (pin "C") (pinfunction "C_C") (pintype "passive"))
      (node (ref "R17") (pin "1") (pinfunction "1_1") (pintype "passive"))
    )
    (net (code "58") (name "Net-(D18-PadC)") (class "Default")
      (node (ref "D18") (pin "C") (pinfunction "C_C") (pintype "passive"))
      (node (ref "R18") (pin "1") (pinfunction "1_1") (pintype "passive"))
    )
    (net (code "59") (name "Net-(D19-PadC)") (class "Default")
      (node (ref "D19") (pin "C") (pinfunction "C_C") (pintype "passive"))
      (node (ref "R19") (pin "1") (pinfunction "1_1") (pintype "passive"))
    )
    (net (code "60") (name "Net-(D20-PadC)") (class "Default")
      (node (ref "D20") (pin "C") (pinfunction "C_C") (pintype "passive"))
      (node (ref "R20") (pin "1") (pinfunction "1_1") (pintype "passive"))
    )
    (net (code "61") (name "Net-(D21-PadC)") (class "Default")
      (node (ref "D21") (pin "C") (pinfunction "C_C") (pintype "passive"))
      (node (ref "R21") (pin "1") (pinfunction "1_1") (pintype "passive"))
    )
    (net (code "62") (name "Net-(D22-PadC)") (class "Default")
      (node (ref "D22") (pin "C") (pinfunction "C_C") (pintype "passive"))
      (node (ref "R22") (pin "1") (pinfunction "1_1") (pintype "passive"))
    )
    (net (code "63") (name "Net-(D23-PadC)") (class "Default")
      (node (ref "D23") (pin "C") (pinfunction "C_C") (pintype "passive"))
      (node (ref "R23") (pin "1") (pinfunction "1_1") (pintype "passive"))
    )
    (net (code "64") (name "Net-(D24-PadC)") (class "Default")
      (node (ref "D24") (pin "C") (pinfunction "C_C") (pintype "passive"))
      (node (ref "R24") (pin "1") (pinfunction "1_1") (pintype "passive"))
    )
    (net (code "65") (name "Net-(D25-PadC)") (class "Default")
      (node (ref "D25") (pin "C") (pinfunction "C_C") (pintype "passive"))
      (node (ref "R25") (pin "1") (pinfunction "1_1") (pintype "passive"))
    )
    (net (code "66") (name "Net-(D26-PadC)") (class "Default")
      (node (ref "D26") (pin "C") (pinfunction "C_C") (pintype "passive"))
      (node (ref "R26") (pin "1") (pinfunction "1_1") (pintype "passive"))
    )
    (net (code "67") (name "Net-(D27-PadC)") (class "Default")
      (node (ref "D27") (pin "C") (pinfunction "C_C") (pintype "passive"))
      (node (ref "R27") (pin "1") (pinfunction "1_1") (pintype "passive"))
    )
    (net (code "68") (name "Net-(D28-PadC)") (class "Default")
      (node (ref "D28") (pin "C") (pinfunction "C_C") (pintype "passive"))
      (node (ref "R28") (pin "1") (pinfunction "1_1") (pintype "passive"))
    )
    (net (code "69") (name "Net-(D29-PadC)") (class "Default")
      (node (ref "D29") (pin "C") (pinfunction "C_C") (pintype "passive"))
      (node (ref "R29") (pin "1") (pinfunction "1_1") (pintype "passive"))
    )
    (net (code "70") (name "Net-(D30-PadC)") (class "Default")
      (node (ref "D30") (pin "C") (pinfunction "C_C") (pintype "passive"))
      (node (ref "R30") (pin "1") (pinfunction "1_1") (pintype "passive"))
    )
    (net (code "71") (name "Net-(D31-PadC)") (class "Default")
      (node (ref "D31") (pin "C") (pinfunction "C_C") (pintype "passive"))
      (node (ref "R31") (pin "1") (pinfunction "1_1") (pintype "passive"))
    )
    (net (code "72") (name "Net-(D32-PadC)") (class "Default")
      (node (ref "D32") (pin "C") (pinfunction "C_C") (pintype "passive"))
      (node (ref "R32") (pin "1") (pinfunction "1_1") (pintype "passive"))
    )
    (net (code "73") (name "Net-(D33-A2)") (class "Default")
      (node (ref "D33") (pin "2") (pinfunction "A2_2") (pintype "passive"))
      (node (ref "R33") (pin "1") (pinfunction "1_1") (pintype "passive"))
    )
    (net (code "74") (name "Net-(D34-A2)") (class "Default")
      (node (ref "D34") (pin "2") (pinfunction "A2_2") (pintype "passive"))
      (node (ref "R34") (pin "1") (pinfunction "1_1") (pintype "passive"))
    )
    (net (code "75") (name "Net-(D35-A2)") (class "Default")
      (node (ref "D35") (pin "2") (pinfunction "A2_2") (pintype "passive"))
      (node (ref "R35") (pin "1") (pinfunction "1_1") (pintype "passive"))
    )
    (net (code "76") (name "Net-(D36-A2)") (class "Default")
      (node (ref "D36") (pin "2") (pinfunction "A2_2") (pintype "passive"))
      (node (ref "R36") (pin "1") (pinfunction "1_1") (pintype "passive"))
    )
    (net (code "77") (name "Net-(D37-K2)") (class "Default")
      (node (ref "D37") (pin "1") (pinfunction "K2_1") (pintype "passive"))
      (node (ref "R37") (pin "1") (pinfunction "1_1") (pintype "passive"))
    )
    (net (code "78") (name "Net-(D38-K2)") (class "Default")
      (node (ref "D38") (pin "1") (pinfunction "K2_1") (pintype "passive"))
      (node (ref "R38") (pin "1") (pinfunction "1_1") (pintype "passive"))
    )
    (net (code "79") (name "Net-(D40-A2)") (class "Default")
      (node (ref "D40") (pin "2") (pinfunction "A2_2") (pintype "passive"))
      (node (ref "R40") (pin "1") (pinfunction "1_1") (pintype "passive"))
    )
    (net (code "80") (name "Net-(D41-K2)") (class "Default")
      (node (ref "D41") (pin "1") (pinfunction "K2_1") (pintype "passive"))
      (node (ref "R42") (pin "2") (pinfunction "2_2") (pintype "passive"))
    )
    (net (code "81") (name "Net-(D42-K2)") (class "Default")
      (node (ref "D42") (pin "1") (pinfunction "K2_1") (pintype "passive"))
      (node (ref "R43") (pin "2") (pinfunction "2_2") (pintype "passive"))
    )
    (net (code "82") (name "Net-(D43-K2)") (class "Default")
      (node (ref "D43") (pin "1") (pinfunction "K2_1") (pintype "passive"))
      (node (ref "R44") (pin "2") (pinfunction "2_2") (pintype "passive"))
    )
    (net (code "83") (name "Net-(D44-K2)") (class "Default")
      (node (ref "D44") (pin "1") (pinfunction "K2_1") (pintype "passive"))
      (node (ref "R45") (pin "2") (pinfunction "2_2") (pintype "passive"))
    )
    (net (code "84") (name "Net-(D45-K2)") (class "Default")
      (node (ref "D45") (pin "1") (pinfunction "K2_1") (pintype "passive"))
      (node (ref "R46") (pin "2") (pinfunction "2_2") (pintype "passive"))
    )
    (net (code "85") (name "Net-(D46-K2)") (class "Default")
      (node (ref "D46") (pin "1") (pinfunction "K2_1") (pintype "passive"))
      (node (ref "R47") (pin "2") (pinfunction "2_2") (pintype "passive"))
    )
    (net (code "86") (name "Net-(D47-K2)") (class "Default")
      (node (ref "D47") (pin "1") (pinfunction "K2_1") (pintype "passive"))
      (node (ref "R48") (pin "2") (pinfunction "2_2") (pintype "passive"))
    )
    (net (code "87") (name "Net-(D48-K2)") (class "Default")
      (node (ref "D48") (pin "1") (pinfunction "K2_1") (pintype "passive"))
      (node (ref "R49") (pin "2") (pinfunction "2_2") (pintype "passive"))
    )
    (net (code "88") (name "Net-(D49-K2)") (class "Default")
      (node (ref "D49") (pin "1") (pinfunction "K2_1") (pintype "passive"))
      (node (ref "R50") (pin "2") (pinfunction "2_2") (pintype "passive"))
    )
    (net (code "89") (name "Net-(D50-K2)") (class "Default")
      (node (ref "D50") (pin "1") (pinfunction "K2_1") (pintype "passive"))
      (node (ref "R51") (pin "2") (pinfunction "2_2") (pintype "passive"))
    )
    (net (code "90") (name "Net-(D51-K2)") (class "Default")
      (node (ref "D51") (pin "1") (pinfunction "K2_1") (pintype "passive"))
      (node (ref "R52") (pin "2") (pinfunction "2_2") (pintype "passive"))
    )
    (net (code "91") (name "Net-(D52-K2)") (class "Default")
      (node (ref "D52") (pin "1") (pinfunction "K2_1") (pintype "passive"))
      (node (ref "R53") (pin "2") (pinfunction "2_2") (pintype "passive"))
    )
    (net (code "92") (name "Net-(D53-K2)") (class "Default")
      (node (ref "D53") (pin "1") (pinfunction "K2_1") (pintype "passive"))
      (node (ref "R54") (pin "2") (pinfunction "2_2") (pintype "passive"))
    )
    (net (code "93") (name "Net-(D54-K2)") (class "Default")
      (node (ref "D54") (pin "1") (pinfunction "K2_1") (pintype "passive"))
      (node (ref "R55") (pin "2") (pinfunction "2_2") (pintype "passive"))
    )
    (net (code "94") (name "Net-(D55-K2)") (class "Default")
      (node (ref "D55") (pin "1") (pinfunction "K2_1") (pintype "passive"))
      (node (ref "R56") (pin "2") (pinfunction "2_2") (pintype "passive"))
    )
    (net (code "95") (name "Net-(D56-K2)") (class "Default")
      (node (ref "D56") (pin "1") (pinfunction "K2_1") (pintype "passive"))
      (node (ref "R57") (pin "2") (pinfunction "2_2") (pintype "passive"))
    )
    (net (code "96") (name "Net-(IC1A-B1)") (class "Default")
      (node (ref "IC1") (pin "6") (pinfunction "B1_6") (pintype "input"))
      (node (ref "IC4") (pin "3") (pinfunction "O_3") (pintype "output"))
    )
    (net (code "97") (name "Net-(IC1A-B2)") (class "Default")
      (node (ref "IC1") (pin "2") (pinfunction "B2_2") (pintype "input"))
      (node (ref "IC4") (pin "6") (pinfunction "O_6") (pintype "output"))
    )
    (net (code "98") (name "Net-(IC1A-B3)") (class "Default")
      (node (ref "IC1") (pin "15") (pinfunction "B3_15") (pintype "input"))
      (node (ref "IC4") (pin "8") (pinfunction "O_8") (pintype "output"))
    )
    (net (code "99") (name "Net-(IC1A-B4)") (class "Default")
      (node (ref "IC1") (pin "11") (pinfunction "B4_11") (pintype "input"))
      (node (ref "IC4") (pin "11") (pinfunction "O_11") (pintype "output"))
    )
    (net (code "100") (name "Net-(IC1A-C0)") (class "Default")
      (node (ref "IC1") (pin "7") (pinfunction "C0_7") (pintype "input"))
      (node (ref "IC39") (pin "11") (pinfunction "O_11") (pintype "output"))
    )
    (net (code "101") (name "Net-(IC1A-C4)") (class "Default")
      (node (ref "IC1") (pin "9") (pinfunction "C4_9") (pintype "output"))
      (node (ref "IC2") (pin "7") (pinfunction "C0_7") (pintype "input"))
    )
    (net (code "102") (name "Net-(IC2A-B1)") (class "Default")
      (node (ref "IC2") (pin "6") (pinfunction "B1_6") (pintype "input"))
      (node (ref "IC5") (pin "3") (pinfunction "O_3") (pintype "output"))
    )
    (net (code "103") (name "Net-(IC2A-B2)") (class "Default")
      (node (ref "IC2") (pin "2") (pinfunction "B2_2") (pintype "input"))
      (node (ref "IC5") (pin "6") (pinfunction "O_6") (pintype "output"))
    )
    (net (code "104") (name "Net-(IC2A-B3)") (class "Default")
      (node (ref "IC2") (pin "15") (pinfunction "B3_15") (pintype "input"))
      (node (ref "IC5") (pin "8") (pinfunction "O_8") (pintype "output"))
    )
    (net (code "105") (name "Net-(IC2A-B4)") (class "Default")
      (node (ref "IC2") (pin "11") (pinfunction "B4_11") (pintype "input"))
      (node (ref "IC5") (pin "11") (pinfunction "O_11") (pintype "output"))
    )
    (net (code "106") (name "Net-(IC6A-O)") (class "Default")
      (node (ref "IC6") (pin "3") (pinfunction "O_3") (pintype "output"))
      (node (ref "IC7") (pin "1") (pinfunction "I0_1") (pintype "input"))
    )
    (net (code "107") (name "Net-(IC6B-O)") (class "Default")
      (node (ref "IC6") (pin "6") (pinfunction "O_6") (pintype "output"))
      (node (ref "IC7") (pin "2") (pinfunction "I1_2") (pintype "input"))
    )
    (net (code "108") (name "Net-(IC6C-O)") (class "Default")
      (node (ref "IC6") (pin "8") (pinfunction "O_8") (pintype "output"))
      (node (ref "IC7") (pin "4") (pinfunction "I0_4") (pintype "input"))
    )
    (net (code "109") (name "Net-(IC6D-O)") (class "Default")
      (node (ref "IC6") (pin "11") (pinfunction "O_11") (pintype "output"))
      (node (ref "IC7") (pin "5") (pinfunction "I1_5") (pintype "input"))
    )
    (net (code "110") (name "Net-(IC7A-O)") (class "Default")
      (node (ref "IC7") (pin "3") (pinfunction "O_3") (pintype "output"))
      (node (ref "IC7") (pin "9") (pinfunction "I0_9") (pintype "input"))
    )
    (net (code "111") (name "Net-(IC7B-O)") (class "Default")
      (node (ref "IC7") (pin "10") (pinfunction "I1_10") (pintype "input"))
      (node (ref "IC7") (pin "6") (pinfunction "O_6") (pintype "output"))
    )
    (net (code "112") (name "Net-(IC7D-I1)") (class "Default")
      (node (ref "IC7") (pin "13") (pinfunction "I1_13") (pintype "input"))
      (node (ref "IC9") (pin "3") (pinfunction "O_3") (pintype "output"))
    )
    (net (code "113") (name "Net-(IC9C-I0)") (class "Default")
      (node (ref "IC9") (pin "10") (pinfunction "I1_10") (pintype "input"))
      (node (ref "IC9") (pin "13") (pinfunction "I1_13") (pintype "input"))
      (node (ref "IC9") (pin "9") (pinfunction "I0_9") (pintype "input"))
    )
    (net (code "114") (name "Net-(IC10A-I0)") (class "Default")
      (node (ref "IC10") (pin "1") (pinfunction "I0_1") (pintype "input"))
      (node (ref "IC8") (pin "2") (pinfunction "O_2") (pintype "output"))
    )
    (net (code "115") (name "Net-(IC10A-I1)") (class "Default")
      (node (ref "IC10") (pin "2") (pinfunction "I1_2") (pintype "input"))
      (node (ref "IC8") (pin "4") (pinfunction "O_4") (pintype "output"))
    )
    (net (code "116") (name "Net-(IC10A-O)") (class "Default")
      (node (ref "IC10") (pin "3") (pinfunction "O_3") (pintype "output"))
      (node (ref "IC10") (pin "4") (pinfunction "I0_4") (pintype "input"))
    )
    (net (code "117") (name "Net-(IC10B-I1)") (class "Default")
      (node (ref "IC10") (pin "5") (pinfunction "I1_5") (pintype "input"))
      (node (ref "IC8") (pin "6") (pinfunction "O_6") (pintype "output"))
    )
    (net (code "118") (name "Net-(IC10B-O)") (class "Default")
      (node (ref "IC10") (pin "12") (pinfunction "I0_12") (pintype "input"))
      (node (ref "IC10") (pin "6") (pinfunction "O_6") (pintype "output"))
    )
    (net (code "119") (name "Net-(IC10C-I0)") (class "Default")
      (node (ref "IC10") (pin "9") (pinfunction "I0_9") (pintype "input"))
      (node (ref "IC8") (pin "8") (pinfunction "O_8") (pintype "output"))
    )
    (net (code "120") (name "Net-(IC10C-I1)") (class "Default")
      (node (ref "IC10") (pin "10") (pinfunction "I1_10") (pintype "input"))
      (node (ref "IC8") (pin "10") (pinfunction "O_10") (pintype "output"))
    )
    (net (code "121") (name "Net-(IC10C-O)") (class "Default")
      (node (ref "IC10") (pin "13") (pinfunction "I1_13") (pintype "input"))
      (node (ref "IC10") (pin "8") (pinfunction "O_8") (pintype "output"))
    )
    (net (code "122") (name "Net-(IC10D-O)") (class "Default")
      (node (ref "IC10") (pin "11") (pinfunction "O_11") (pintype "output"))
      (node (ref "IC4") (pin "10") (pinfunction "I1_10") (pintype "input"))
      (node (ref "IC4") (pin "13") (pinfunction "I1_13") (pintype "input"))
      (node (ref "IC4") (pin "2") (pinfunction "I1_2") (pintype "input"))
      (node (ref "IC4") (pin "5") (pinfunction "I1_5") (pintype "input"))
      (node (ref "IC5") (pin "10") (pinfunction "I1_10") (pintype "input"))
      (node (ref "IC5") (pin "13") (pinfunction "I1_13") (pintype "input"))
      (node (ref "IC5") (pin "2") (pinfunction "I1_2") (pintype "input"))
      (node (ref "IC5") (pin "5") (pinfunction "I1_5") (pintype "input"))
    )
    (net (code "123") (name "Net-(IC11A-I0)") (class "Default")
      (node (ref "D17") (pin "A") (pinfunction "A_A") (pintype "passive"))
      (node (ref "IC1") (pin "5") (pinfunction "A1_5") (pintype "input"))
      (node (ref "IC11") (pin "1") (pinfunction "I0_1") (pintype "input"))
      (node (ref "IC17") (pin "1") (pinfunction "I0_1") (pintype "input"))
      (node (ref "IC19") (pin "1") (pinfunction "I0_1") (pintype "input"))
      (node (ref "IC24") (pin "17") (pinfunction "B2_17") (pintype "bidirectional"))
      (node (ref "IC25") (pin "11") (pinfunction "B8_11") (pintype "bidirectional"))
      (node (ref "SV_ALU_1") (pin "19") (pinfunction "19_19") (pintype "passive"))
    )
    (net (code "124") (name "Net-(IC11A-I1)") (class "Default")
      (node (ref "D25") (pin "A") (pinfunction "A_A") (pintype "passive"))
      (node (ref "IC11") (pin "2") (pinfunction "I1_2") (pintype "input"))
      (node (ref "IC17") (pin "2") (pinfunction "I1_2") (pintype "input"))
      (node (ref "IC19") (pin "2") (pinfunction "I1_2") (pintype "input"))
      (node (ref "IC4") (pin "1") (pinfunction "I0_1") (pintype "input"))
      (node (ref "SV_ALU_1") (pin "3") (pinfunction "3_3") (pintype "passive"))
    )
    (net (code "125") (name "Net-(IC11A-O)") (class "Default")
      (node (ref "IC11") (pin "3") (pinfunction "O_3") (pintype "output"))
      (node (ref "IC14") (pin "18") (pinfunction "B1_18") (pintype "bidirectional"))
    )
    (net (code "126") (name "Net-(IC11B-I0)") (class "Default")
      (node (ref "D18") (pin "A") (pinfunction "A_A") (pintype "passive"))
      (node (ref "IC1") (pin "3") (pinfunction "A2_3") (pintype "input"))
      (node (ref "IC11") (pin "4") (pinfunction "I0_4") (pintype "input"))
      (node (ref "IC17") (pin "4") (pinfunction "I0_4") (pintype "input"))
      (node (ref "IC19") (pin "4") (pinfunction "I0_4") (pintype "input"))
      (node (ref "IC22") (pin "18") (pinfunction "B1_18") (pintype "bidirectional"))
      (node (ref "IC23") (pin "18") (pinfunction "B1_18") (pintype "bidirectional"))
      (node (ref "IC24") (pin "16") (pinfunction "B3_16") (pintype "bidirectional"))
      (node (ref "IC25") (pin "18") (pinfunction "B1_18") (pintype "bidirectional"))
      (node (ref "SV_ALU_1") (pin "21") (pinfunction "21_21") (pintype "passive"))
    )
    (net (code "127") (name "Net-(IC11B-I1)") (class "Default")
      (node (ref "D26") (pin "A") (pinfunction "A_A") (pintype "passive"))
      (node (ref "IC11") (pin "5") (pinfunction "I1_5") (pintype "input"))
      (node (ref "IC17") (pin "5") (pinfunction "I1_5") (pintype "input"))
      (node (ref "IC19") (pin "5") (pinfunction "I1_5") (pintype "input"))
      (node (ref "IC4") (pin "4") (pinfunction "I0_4") (pintype "input"))
      (node (ref "SV_ALU_1") (pin "5") (pinfunction "5_5") (pintype "passive"))
    )
    (net (code "128") (name "Net-(IC11B-O)") (class "Default")
      (node (ref "IC11") (pin "6") (pinfunction "O_6") (pintype "output"))
      (node (ref "IC14") (pin "17") (pinfunction "B2_17") (pintype "bidirectional"))
    )
    (net (code "129") (name "Net-(IC11C-I0)") (class "Default")
      (node (ref "D19") (pin "A") (pinfunction "A_A") (pintype "passive"))
      (node (ref "IC1") (pin "14") (pinfunction "A3_14") (pintype "input"))
      (node (ref "IC11") (pin "9") (pinfunction "I0_9") (pintype "input"))
      (node (ref "IC17") (pin "9") (pinfunction "I0_9") (pintype "input"))
      (node (ref "IC19") (pin "9") (pinfunction "I0_9") (pintype "input"))
      (node (ref "IC22") (pin "17") (pinfunction "B2_17") (pintype "bidirectional"))
      (node (ref "IC23") (pin "17") (pinfunction "B2_17") (pintype "bidirectional"))
      (node (ref "IC24") (pin "15") (pinfunction "B4_15") (pintype "bidirectional"))
      (node (ref "IC25") (pin "17") (pinfunction "B2_17") (pintype "bidirectional"))
      (node (ref "SV_ALU_1") (pin "23") (pinfunction "23_23") (pintype "passive"))
    )
    (net (code "130") (name "Net-(IC11C-I1)") (class "Default")
      (node (ref "D27") (pin "A") (pinfunction "A_A") (pintype "passive"))
      (node (ref "IC11") (pin "10") (pinfunction "I1_10") (pintype "input"))
      (node (ref "IC17") (pin "10") (pinfunction "I1_10") (pintype "input"))
      (node (ref "IC19") (pin "10") (pinfunction "I1_10") (pintype "input"))
      (node (ref "IC4") (pin "9") (pinfunction "I0_9") (pintype "input"))
      (node (ref "SV_ALU_1") (pin "7") (pinfunction "7_7") (pintype "passive"))
    )
    (net (code "131") (name "Net-(IC11C-O)") (class "Default")
      (node (ref "IC11") (pin "8") (pinfunction "O_8") (pintype "output"))
      (node (ref "IC14") (pin "16") (pinfunction "B3_16") (pintype "bidirectional"))
    )
    (net (code "132") (name "Net-(IC11D-I0)") (class "Default")
      (node (ref "D20") (pin "A") (pinfunction "A_A") (pintype "passive"))
      (node (ref "IC1") (pin "12") (pinfunction "A4_12") (pintype "input"))
      (node (ref "IC11") (pin "12") (pinfunction "I0_12") (pintype "input"))
      (node (ref "IC17") (pin "12") (pinfunction "I0_12") (pintype "input"))
      (node (ref "IC19") (pin "12") (pinfunction "I0_12") (pintype "input"))
      (node (ref "IC22") (pin "16") (pinfunction "B3_16") (pintype "bidirectional"))
      (node (ref "IC23") (pin "16") (pinfunction "B3_16") (pintype "bidirectional"))
      (node (ref "IC24") (pin "14") (pinfunction "B5_14") (pintype "bidirectional"))
      (node (ref "IC25") (pin "16") (pinfunction "B3_16") (pintype "bidirectional"))
      (node (ref "SV_ALU_1") (pin "25") (pinfunction "25_25") (pintype "passive"))
    )
    (net (code "133") (name "Net-(IC11D-I1)") (class "Default")
      (node (ref "D28") (pin "A") (pinfunction "A_A") (pintype "passive"))
      (node (ref "IC11") (pin "13") (pinfunction "I1_13") (pintype "input"))
      (node (ref "IC17") (pin "13") (pinfunction "I1_13") (pintype "input"))
      (node (ref "IC19") (pin "13") (pinfunction "I1_13") (pintype "input"))
      (node (ref "IC4") (pin "12") (pinfunction "I0_12") (pintype "input"))
      (node (ref "SV_ALU_1") (pin "9") (pinfunction "9_9") (pintype "passive"))
    )
    (net (code "134") (name "Net-(IC11D-O)") (class "Default")
      (node (ref "IC11") (pin "11") (pinfunction "O_11") (pintype "output"))
      (node (ref "IC14") (pin "15") (pinfunction "B4_15") (pintype "bidirectional"))
    )
    (net (code "135") (name "Net-(IC12A-A2)") (class "Default")
      (node (ref "D2") (pin "A") (pinfunction "A_A") (pintype "passive"))
      (node (ref "IC12") (pin "3") (pinfunction "A2_3") (pintype "bidirectional"))
      (node (ref "IC14") (pin "3") (pinfunction "A2_3") (pintype "bidirectional"))
      (node (ref "IC15") (pin "3") (pinfunction "A2_3") (pintype "bidirectional"))
      (node (ref "IC16") (pin "3") (pinfunction "A2_3") (pintype "bidirectional"))
      (node (ref "IC21") (pin "3") (pinfunction "A2_3") (pintype "bidirectional"))
      (node (ref "IC22") (pin "3") (pinfunction "A2_3") (pintype "bidirectional"))
      (node (ref "IC23") (pin "3") (pinfunction "A2_3") (pintype "bidirectional"))
      (node (ref "IC24") (pin "3") (pinfunction "A2_3") (pintype "bidirectional"))
      (node (ref "IC25") (pin "3") (pinfunction "A2_3") (pintype "bidirectional"))
      (node (ref "IC36") (pin "4") (pinfunction "D2_4") (pintype "input"))
      (node (ref "IC37") (pin "3") (pinfunction "I1_3") (pintype "input"))
    )
    (net (code "136") (name "Net-(IC12A-A3)") (class "Default")
      (node (ref "D3") (pin "A") (pinfunction "A_A") (pintype "passive"))
      (node (ref "IC12") (pin "4") (pinfunction "A3_4") (pintype "bidirectional"))
      (node (ref "IC14") (pin "4") (pinfunction "A3_4") (pintype "bidirectional"))
      (node (ref "IC15") (pin "4") (pinfunction "A3_4") (pintype "bidirectional"))
      (node (ref "IC16") (pin "4") (pinfunction "A3_4") (pintype "bidirectional"))
      (node (ref "IC21") (pin "4") (pinfunction "A3_4") (pintype "bidirectional"))
      (node (ref "IC22") (pin "4") (pinfunction "A3_4") (pintype "bidirectional"))
      (node (ref "IC23") (pin "4") (pinfunction "A3_4") (pintype "bidirectional"))
      (node (ref "IC24") (pin "4") (pinfunction "A3_4") (pintype "bidirectional"))
      (node (ref "IC25") (pin "4") (pinfunction "A3_4") (pintype "bidirectional"))
      (node (ref "IC36") (pin "7") (pinfunction "D3_7") (pintype "input"))
      (node (ref "IC37") (pin "5") (pinfunction "I0_5") (pintype "input"))
    )
    (net (code "137") (name "Net-(IC12A-A4)") (class "Default")
      (node (ref "D4") (pin "A") (pinfunction "A_A") (pintype "passive"))
      (node (ref "IC12") (pin "5") (pinfunction "A4_5") (pintype "bidirectional"))
      (node (ref "IC14") (pin "5") (pinfunction "A4_5") (pintype "bidirectional"))
      (node (ref "IC15") (pin "5") (pinfunction "A4_5") (pintype "bidirectional"))
      (node (ref "IC16") (pin "5") (pinfunction "A4_5") (pintype "bidirectional"))
      (node (ref "IC21") (pin "5") (pinfunction "A4_5") (pintype "bidirectional"))
      (node (ref "IC22") (pin "5") (pinfunction "A4_5") (pintype "bidirectional"))
      (node (ref "IC23") (pin "5") (pinfunction "A4_5") (pintype "bidirectional"))
      (node (ref "IC24") (pin "5") (pinfunction "A4_5") (pintype "bidirectional"))
      (node (ref "IC25") (pin "5") (pinfunction "A4_5") (pintype "bidirectional"))
      (node (ref "IC36") (pin "8") (pinfunction "D4_8") (pintype "input"))
      (node (ref "IC37") (pin "6") (pinfunction "I1_6") (pintype "input"))
    )
    (net (code "138") (name "Net-(IC12A-A5)") (class "Default")
      (node (ref "D5") (pin "A") (pinfunction "A_A") (pintype "passive"))
      (node (ref "IC12") (pin "6") (pinfunction "A5_6") (pintype "bidirectional"))
      (node (ref "IC14") (pin "6") (pinfunction "A5_6") (pintype "bidirectional"))
      (node (ref "IC15") (pin "6") (pinfunction "A5_6") (pintype "bidirectional"))
      (node (ref "IC16") (pin "6") (pinfunction "A5_6") (pintype "bidirectional"))
      (node (ref "IC21") (pin "6") (pinfunction "A5_6") (pintype "bidirectional"))
      (node (ref "IC22") (pin "6") (pinfunction "A5_6") (pintype "bidirectional"))
      (node (ref "IC23") (pin "6") (pinfunction "A5_6") (pintype "bidirectional"))
      (node (ref "IC24") (pin "6") (pinfunction "A5_6") (pintype "bidirectional"))
      (node (ref "IC25") (pin "6") (pinfunction "A5_6") (pintype "bidirectional"))
      (node (ref "IC36") (pin "13") (pinfunction "D5_13") (pintype "input"))
      (node (ref "IC37") (pin "8") (pinfunction "I0_8") (pintype "input"))
    )
    (net (code "139") (name "Net-(IC12A-A6)") (class "Default")
      (node (ref "D6") (pin "A") (pinfunction "A_A") (pintype "passive"))
      (node (ref "IC12") (pin "7") (pinfunction "A6_7") (pintype "bidirectional"))
      (node (ref "IC14") (pin "7") (pinfunction "A6_7") (pintype "bidirectional"))
      (node (ref "IC15") (pin "7") (pinfunction "A6_7") (pintype "bidirectional"))
      (node (ref "IC16") (pin "7") (pinfunction "A6_7") (pintype "bidirectional"))
      (node (ref "IC21") (pin "7") (pinfunction "A6_7") (pintype "bidirectional"))
      (node (ref "IC22") (pin "7") (pinfunction "A6_7") (pintype "bidirectional"))
      (node (ref "IC23") (pin "7") (pinfunction "A6_7") (pintype "bidirectional"))
      (node (ref "IC24") (pin "7") (pinfunction "A6_7") (pintype "bidirectional"))
      (node (ref "IC25") (pin "7") (pinfunction "A6_7") (pintype "bidirectional"))
      (node (ref "IC36") (pin "14") (pinfunction "D6_14") (pintype "input"))
      (node (ref "IC37") (pin "9") (pinfunction "I1_9") (pintype "input"))
    )
    (net (code "140") (name "Net-(IC12A-A7)") (class "Default")
      (node (ref "D7") (pin "A") (pinfunction "A_A") (pintype "passive"))
      (node (ref "IC12") (pin "8") (pinfunction "A7_8") (pintype "bidirectional"))
      (node (ref "IC14") (pin "8") (pinfunction "A7_8") (pintype "bidirectional"))
      (node (ref "IC15") (pin "8") (pinfunction "A7_8") (pintype "bidirectional"))
      (node (ref "IC16") (pin "8") (pinfunction "A7_8") (pintype "bidirectional"))
      (node (ref "IC21") (pin "8") (pinfunction "A7_8") (pintype "bidirectional"))
      (node (ref "IC22") (pin "8") (pinfunction "A7_8") (pintype "bidirectional"))
      (node (ref "IC23") (pin "8") (pinfunction "A7_8") (pintype "bidirectional"))
      (node (ref "IC24") (pin "8") (pinfunction "A7_8") (pintype "bidirectional"))
      (node (ref "IC25") (pin "8") (pinfunction "A7_8") (pintype "bidirectional"))
      (node (ref "IC36") (pin "17") (pinfunction "D7_17") (pintype "input"))
      (node (ref "IC37") (pin "11") (pinfunction "I0_11") (pintype "input"))
    )
    (net (code "141") (name "Net-(IC12A-A8)") (class "Default")
      (node (ref "D8") (pin "A") (pinfunction "A_A") (pintype "passive"))
      (node (ref "IC12") (pin "9") (pinfunction "A8_9") (pintype "bidirectional"))
      (node (ref "IC14") (pin "9") (pinfunction "A8_9") (pintype "bidirectional"))
      (node (ref "IC15") (pin "9") (pinfunction "A8_9") (pintype "bidirectional"))
      (node (ref "IC16") (pin "9") (pinfunction "A8_9") (pintype "bidirectional"))
      (node (ref "IC21") (pin "9") (pinfunction "A8_9") (pintype "bidirectional"))
      (node (ref "IC22") (pin "9") (pinfunction "A8_9") (pintype "bidirectional"))
      (node (ref "IC23") (pin "9") (pinfunction "A8_9") (pintype "bidirectional"))
      (node (ref "IC24") (pin "9") (pinfunction "A8_9") (pintype "bidirectional"))
      (node (ref "IC25") (pin "9") (pinfunction "A8_9") (pintype "bidirectional"))
      (node (ref "IC36") (pin "18") (pinfunction "D8_18") (pintype "input"))
      (node (ref "IC37") (pin "12") (pinfunction "I1_12") (pintype "input"))
    )
    (net (code "142") (name "Net-(IC12A-B1)") (class "Default")
      (node (ref "IC1") (pin "4") (pinfunction "S1_4") (pintype "output"))
      (node (ref "IC12") (pin "18") (pinfunction "B1_18") (pintype "bidirectional"))
    )
    (net (code "143") (name "Net-(IC12A-B2)") (class "Default")
      (node (ref "IC1") (pin "1") (pinfunction "S2_1") (pintype "output"))
      (node (ref "IC12") (pin "17") (pinfunction "B2_17") (pintype "bidirectional"))
    )
    (net (code "144") (name "Net-(IC12A-B3)") (class "Default")
      (node (ref "IC1") (pin "13") (pinfunction "S3_13") (pintype "output"))
      (node (ref "IC12") (pin "16") (pinfunction "B3_16") (pintype "bidirectional"))
    )
    (net (code "145") (name "Net-(IC12A-B4)") (class "Default")
      (node (ref "IC1") (pin "10") (pinfunction "S4_10") (pintype "output"))
      (node (ref "IC12") (pin "15") (pinfunction "B4_15") (pintype "bidirectional"))
    )
    (net (code "146") (name "Net-(IC12A-B5)") (class "Default")
      (node (ref "IC12") (pin "14") (pinfunction "B5_14") (pintype "bidirectional"))
      (node (ref "IC2") (pin "4") (pinfunction "S1_4") (pintype "output"))
    )
    (net (code "147") (name "Net-(IC12A-B6)") (class "Default")
      (node (ref "IC12") (pin "13") (pinfunction "B6_13") (pintype "bidirectional"))
      (node (ref "IC2") (pin "1") (pinfunction "S2_1") (pintype "output"))
    )
    (net (code "148") (name "Net-(IC12A-B7)") (class "Default")
      (node (ref "IC12") (pin "12") (pinfunction "B7_12") (pintype "bidirectional"))
      (node (ref "IC2") (pin "13") (pinfunction "S3_13") (pintype "output"))
    )
    (net (code "149") (name "Net-(IC12A-B8)") (class "Default")
      (node (ref "IC12") (pin "11") (pinfunction "B8_11") (pintype "bidirectional"))
      (node (ref "IC2") (pin "10") (pinfunction "S4_10") (pintype "output"))
    )
    (net (code "150") (name "Net-(IC12A-G)") (class "Default")
      (node (ref "IC12") (pin "19") (pinfunction "G_19") (pintype "input"))
      (node (ref "IC7") (pin "8") (pinfunction "O_8") (pintype "output"))
    )
    (net (code "151") (name "Net-(IC13A-I0)") (class "Default")
      (node (ref "D21") (pin "A") (pinfunction "A_A") (pintype "passive"))
      (node (ref "IC13") (pin "1") (pinfunction "I0_1") (pintype "input"))
      (node (ref "IC18") (pin "1") (pinfunction "I0_1") (pintype "input"))
      (node (ref "IC2") (pin "5") (pinfunction "A1_5") (pintype "input"))
      (node (ref "IC20") (pin "1") (pinfunction "I0_1") (pintype "input"))
      (node (ref "IC22") (pin "15") (pinfunction "B4_15") (pintype "bidirectional"))
      (node (ref "IC23") (pin "15") (pinfunction "B4_15") (pintype "bidirectional"))
      (node (ref "IC24") (pin "13") (pinfunction "B6_13") (pintype "bidirectional"))
      (node (ref "IC25") (pin "15") (pinfunction "B4_15") (pintype "bidirectional"))
      (node (ref "SV_ALU_1") (pin "27") (pinfunction "27_27") (pintype "passive"))
    )
    (net (code "152") (name "Net-(IC13A-I1)") (class "Default")
      (node (ref "D29") (pin "A") (pinfunction "A_A") (pintype "passive"))
      (node (ref "IC13") (pin "2") (pinfunction "I1_2") (pintype "input"))
      (node (ref "IC18") (pin "2") (pinfunction "I1_2") (pintype "input"))
      (node (ref "IC20") (pin "2") (pinfunction "I1_2") (pintype "input"))
      (node (ref "IC5") (pin "1") (pinfunction "I0_1") (pintype "input"))
      (node (ref "SV_ALU_1") (pin "11") (pinfunction "11_11") (pintype "passive"))
    )
    (net (code "153") (name "Net-(IC13A-O)") (class "Default")
      (node (ref "IC13") (pin "3") (pinfunction "O_3") (pintype "output"))
      (node (ref "IC14") (pin "14") (pinfunction "B5_14") (pintype "bidirectional"))
    )
    (net (code "154") (name "Net-(IC13B-I0)") (class "Default")
      (node (ref "D22") (pin "A") (pinfunction "A_A") (pintype "passive"))
      (node (ref "IC13") (pin "4") (pinfunction "I0_4") (pintype "input"))
      (node (ref "IC18") (pin "4") (pinfunction "I0_4") (pintype "input"))
      (node (ref "IC2") (pin "3") (pinfunction "A2_3") (pintype "input"))
      (node (ref "IC20") (pin "4") (pinfunction "I0_4") (pintype "input"))
      (node (ref "IC22") (pin "14") (pinfunction "B5_14") (pintype "bidirectional"))
      (node (ref "IC23") (pin "14") (pinfunction "B5_14") (pintype "bidirectional"))
      (node (ref "IC24") (pin "12") (pinfunction "B7_12") (pintype "bidirectional"))
      (node (ref "IC25") (pin "14") (pinfunction "B5_14") (pintype "bidirectional"))
      (node (ref "SV_ALU_1") (pin "29") (pinfunction "29_29") (pintype "passive"))
    )
    (net (code "155") (name "Net-(IC13B-I1)") (class "Default")
      (node (ref "D30") (pin "A") (pinfunction "A_A") (pintype "passive"))
      (node (ref "IC13") (pin "5") (pinfunction "I1_5") (pintype "input"))
      (node (ref "IC18") (pin "5") (pinfunction "I1_5") (pintype "input"))
      (node (ref "IC20") (pin "5") (pinfunction "I1_5") (pintype "input"))
      (node (ref "IC5") (pin "4") (pinfunction "I0_4") (pintype "input"))
      (node (ref "SV_ALU_1") (pin "13") (pinfunction "13_13") (pintype "passive"))
    )
    (net (code "156") (name "Net-(IC13B-O)") (class "Default")
      (node (ref "IC13") (pin "6") (pinfunction "O_6") (pintype "output"))
      (node (ref "IC14") (pin "13") (pinfunction "B6_13") (pintype "bidirectional"))
    )
    (net (code "157") (name "Net-(IC13C-I0)") (class "Default")
      (node (ref "D23") (pin "A") (pinfunction "A_A") (pintype "passive"))
      (node (ref "IC13") (pin "9") (pinfunction "I0_9") (pintype "input"))
      (node (ref "IC18") (pin "9") (pinfunction "I0_9") (pintype "input"))
      (node (ref "IC2") (pin "14") (pinfunction "A3_14") (pintype "input"))
      (node (ref "IC20") (pin "9") (pinfunction "I0_9") (pintype "input"))
      (node (ref "IC22") (pin "13") (pinfunction "B6_13") (pintype "bidirectional"))
      (node (ref "IC23") (pin "13") (pinfunction "B6_13") (pintype "bidirectional"))
      (node (ref "IC24") (pin "11") (pinfunction "B8_11") (pintype "bidirectional"))
      (node (ref "IC25") (pin "13") (pinfunction "B6_13") (pintype "bidirectional"))
      (node (ref "SV_ALU_1") (pin "31") (pinfunction "31_31") (pintype "passive"))
    )
    (net (code "158") (name "Net-(IC13C-I1)") (class "Default")
      (node (ref "D31") (pin "A") (pinfunction "A_A") (pintype "passive"))
      (node (ref "IC13") (pin "10") (pinfunction "I1_10") (pintype "input"))
      (node (ref "IC18") (pin "10") (pinfunction "I1_10") (pintype "input"))
      (node (ref "IC20") (pin "10") (pinfunction "I1_10") (pintype "input"))
      (node (ref "IC5") (pin "9") (pinfunction "I0_9") (pintype "input"))
      (node (ref "SV_ALU_1") (pin "15") (pinfunction "15_15") (pintype "passive"))
    )
    (net (code "159") (name "Net-(IC13C-O)") (class "Default")
      (node (ref "IC13") (pin "8") (pinfunction "O_8") (pintype "output"))
      (node (ref "IC14") (pin "12") (pinfunction "B7_12") (pintype "bidirectional"))
    )
    (net (code "160") (name "Net-(IC13D-I0)") (class "Default")
      (node (ref "D24") (pin "A") (pinfunction "A_A") (pintype "passive"))
      (node (ref "IC13") (pin "12") (pinfunction "I0_12") (pintype "input"))
      (node (ref "IC18") (pin "12") (pinfunction "I0_12") (pintype "input"))
      (node (ref "IC2") (pin "12") (pinfunction "A4_12") (pintype "input"))
      (node (ref "IC20") (pin "12") (pinfunction "I0_12") (pintype "input"))
      (node (ref "IC22") (pin "12") (pinfunction "B7_12") (pintype "bidirectional"))
      (node (ref "IC23") (pin "11") (pinfunction "B8_11") (pintype "bidirectional"))
      (node (ref "IC23") (pin "12") (pinfunction "B7_12") (pintype "bidirectional"))
      (node (ref "IC24") (pin "18") (pinfunction "B1_18") (pintype "bidirectional"))
      (node (ref "IC25") (pin "12") (pinfunction "B7_12") (pintype "bidirectional"))
      (node (ref "SV_ALU_1") (pin "33") (pinfunction "33_33") (pintype "passive"))
    )
    (net (code "161") (name "Net-(IC13D-I1)") (class "Default")
      (node (ref "D32") (pin "A") (pinfunction "A_A") (pintype "passive"))
      (node (ref "IC13") (pin "13") (pinfunction "I1_13") (pintype "input"))
      (node (ref "IC18") (pin "13") (pinfunction "I1_13") (pintype "input"))
      (node (ref "IC20") (pin "13") (pinfunction "I1_13") (pintype "input"))
      (node (ref "IC5") (pin "12") (pinfunction "I0_12") (pintype "input"))
      (node (ref "SV_ALU_1") (pin "17") (pinfunction "17_17") (pintype "passive"))
    )
    (net (code "162") (name "Net-(IC13D-O)") (class "Default")
      (node (ref "IC13") (pin "11") (pinfunction "O_11") (pintype "output"))
      (node (ref "IC14") (pin "11") (pinfunction "B8_11") (pintype "bidirectional"))
    )
    (net (code "163") (name "Net-(IC15A-B1)") (class "Default")
      (node (ref "IC15") (pin "18") (pinfunction "B1_18") (pintype "bidirectional"))
      (node (ref "IC17") (pin "3") (pinfunction "O_3") (pintype "output"))
    )
    (net (code "164") (name "Net-(IC15A-B2)") (class "Default")
      (node (ref "IC15") (pin "17") (pinfunction "B2_17") (pintype "bidirectional"))
      (node (ref "IC17") (pin "6") (pinfunction "O_6") (pintype "output"))
    )
    (net (code "165") (name "Net-(IC15A-B3)") (class "Default")
      (node (ref "IC15") (pin "16") (pinfunction "B3_16") (pintype "bidirectional"))
      (node (ref "IC17") (pin "8") (pinfunction "O_8") (pintype "output"))
    )
    (net (code "166") (name "Net-(IC15A-B4)") (class "Default")
      (node (ref "IC15") (pin "15") (pinfunction "B4_15") (pintype "bidirectional"))
      (node (ref "IC17") (pin "11") (pinfunction "O_11") (pintype "output"))
    )
    (net (code "167") (name "Net-(IC15A-B5)") (class "Default")
      (node (ref "IC15") (pin "14") (pinfunction "B5_14") (pintype "bidirectional"))
      (node (ref "IC18") (pin "3") (pinfunction "O_3") (pintype "output"))
    )
    (net (code "168") (name "Net-(IC15A-B6)") (class "Default")
      (node (ref "IC15") (pin "13") (pinfunction "B6_13") (pintype "bidirectional"))
      (node (ref "IC18") (pin "6") (pinfunction "O_6") (pintype "output"))
    )
    (net (code "169") (name "Net-(IC15A-B7)") (class "Default")
      (node (ref "IC15") (pin "12") (pinfunction "B7_12") (pintype "bidirectional"))
      (node (ref "IC18") (pin "8") (pinfunction "O_8") (pintype "output"))
    )
    (net (code "170") (name "Net-(IC15A-B8)") (class "Default")
      (node (ref "IC15") (pin "11") (pinfunction "B8_11") (pintype "bidirectional"))
      (node (ref "IC18") (pin "11") (pinfunction "O_11") (pintype "output"))
    )
    (net (code "171") (name "Net-(IC16A-B1)") (class "Default")
      (node (ref "IC16") (pin "18") (pinfunction "B1_18") (pintype "bidirectional"))
      (node (ref "IC19") (pin "3") (pinfunction "O_3") (pintype "output"))
    )
    (net (code "172") (name "Net-(IC16A-B2)") (class "Default")
      (node (ref "IC16") (pin "17") (pinfunction "B2_17") (pintype "bidirectional"))
      (node (ref "IC19") (pin "6") (pinfunction "O_6") (pintype "output"))
    )
    (net (code "173") (name "Net-(IC16A-B3)") (class "Default")
      (node (ref "IC16") (pin "16") (pinfunction "B3_16") (pintype "bidirectional"))
      (node (ref "IC19") (pin "8") (pinfunction "O_8") (pintype "output"))
    )
    (net (code "174") (name "Net-(IC16A-B4)") (class "Default")
      (node (ref "IC16") (pin "15") (pinfunction "B4_15") (pintype "bidirectional"))
      (node (ref "IC19") (pin "11") (pinfunction "O_11") (pintype "output"))
    )
    (net (code "175") (name "Net-(IC16A-B5)") (class "Default")
      (node (ref "IC16") (pin "14") (pinfunction "B5_14") (pintype "bidirectional"))
      (node (ref "IC20") (pin "3") (pinfunction "O_3") (pintype "output"))
    )
    (net (code "176") (name "Net-(IC16A-B6)") (class "Default")
      (node (ref "IC16") (pin "13") (pinfunction "B6_13") (pintype "bidirectional"))
      (node (ref "IC20") (pin "6") (pinfunction "O_6") (pintype "output"))
    )
    (net (code "177") (name "Net-(IC16A-B7)") (class "Default")
      (node (ref "IC16") (pin "12") (pinfunction "B7_12") (pintype "bidirectional"))
      (node (ref "IC20") (pin "8") (pinfunction "O_8") (pintype "output"))
    )
    (net (code "178") (name "Net-(IC16A-B8)") (class "Default")
      (node (ref "IC16") (pin "11") (pinfunction "B8_11") (pintype "bidirectional"))
      (node (ref "IC20") (pin "11") (pinfunction "O_11") (pintype "output"))
    )
    (net (code "179") (name "Net-(IC21A-B1)") (class "Default")
      (node (ref "IC21") (pin "18") (pinfunction "B1_18") (pintype "bidirectional"))
      (node (ref "IC22") (pin "11") (pinfunction "B8_11") (pintype "bidirectional"))
      (node (ref "R41") (pin "1") (pinfunction "1_1") (pintype "passive"))
    )
    (net (code "180") (name "Net-(IC36A-Q1)") (class "Default")
      (node (ref "D9") (pin "A") (pinfunction "A_A") (pintype "passive"))
      (node (ref "IC36") (pin "2") (pinfunction "Q1_2") (pintype "output"))
      (node (ref "IC38") (pin "2") (pinfunction "A1_2") (pintype "bidirectional"))
    )
    (net (code "181") (name "Net-(IC36A-Q2)") (class "Default")
      (node (ref "D10") (pin "A") (pinfunction "A_A") (pintype "passive"))
      (node (ref "IC36") (pin "5") (pinfunction "Q2_5") (pintype "output"))
      (node (ref "IC38") (pin "3") (pinfunction "A2_3") (pintype "bidirectional"))
    )
    (net (code "182") (name "Net-(IC36A-Q3)") (class "Default")
      (node (ref "D11") (pin "A") (pinfunction "A_A") (pintype "passive"))
      (node (ref "IC36") (pin "6") (pinfunction "Q3_6") (pintype "output"))
      (node (ref "IC38") (pin "4") (pinfunction "A3_4") (pintype "bidirectional"))
    )
    (net (code "183") (name "Net-(IC36A-Q4)") (class "Default")
      (node (ref "D12") (pin "A") (pinfunction "A_A") (pintype "passive"))
      (node (ref "IC36") (pin "9") (pinfunction "Q4_9") (pintype "output"))
      (node (ref "IC38") (pin "5") (pinfunction "A4_5") (pintype "bidirectional"))
    )
    (net (code "184") (name "Net-(IC36A-Q5)") (class "Default")
      (node (ref "D13") (pin "A") (pinfunction "A_A") (pintype "passive"))
      (node (ref "IC36") (pin "12") (pinfunction "Q5_12") (pintype "output"))
      (node (ref "IC38") (pin "6") (pinfunction "A5_6") (pintype "bidirectional"))
    )
    (net (code "185") (name "Net-(IC36A-Q6)") (class "Default")
      (node (ref "D14") (pin "A") (pinfunction "A_A") (pintype "passive"))
      (node (ref "IC36") (pin "15") (pinfunction "Q6_15") (pintype "output"))
      (node (ref "IC38") (pin "7") (pinfunction "A6_7") (pintype "bidirectional"))
    )
    (net (code "186") (name "Net-(IC36A-Q7)") (class "Default")
      (node (ref "D15") (pin "A") (pinfunction "A_A") (pintype "passive"))
      (node (ref "IC36") (pin "16") (pinfunction "Q7_16") (pintype "output"))
      (node (ref "IC38") (pin "8") (pinfunction "A7_8") (pintype "bidirectional"))
    )
    (net (code "187") (name "Net-(IC36A-Q8)") (class "Default")
      (node (ref "D16") (pin "A") (pinfunction "A_A") (pintype "passive"))
      (node (ref "IC36") (pin "19") (pinfunction "Q8_19") (pintype "output"))
      (node (ref "IC38") (pin "9") (pinfunction "A8_9") (pintype "bidirectional"))
    )
    (net (code "188") (name "Net-(IC37A-O)") (class "Default")
      (node (ref "IC37") (pin "1") (pinfunction "O_1") (pintype "output"))
      (node (ref "IC39") (pin "1") (pinfunction "I0_1") (pintype "input"))
    )
    (net (code "189") (name "Net-(IC37B-O)") (class "Default")
      (node (ref "IC37") (pin "4") (pinfunction "O_4") (pintype "output"))
      (node (ref "IC39") (pin "2") (pinfunction "I1_2") (pintype "input"))
    )
    (net (code "190") (name "Net-(IC37C-O)") (class "Default")
      (node (ref "IC37") (pin "10") (pinfunction "O_10") (pintype "output"))
      (node (ref "IC39") (pin "4") (pinfunction "I0_4") (pintype "input"))
    )
    (net (code "191") (name "Net-(IC37D-O)") (class "Default")
      (node (ref "IC37") (pin "13") (pinfunction "O_13") (pintype "output"))
      (node (ref "IC39") (pin "5") (pinfunction "I1_5") (pintype "input"))
    )
    (net (code "192") (name "Net-(IC39A-O)") (class "Default")
      (node (ref "IC39") (pin "3") (pinfunction "O_3") (pintype "output"))
      (node (ref "IC39") (pin "9") (pinfunction "I0_9") (pintype "input"))
    )
    (net (code "193") (name "Net-(IC39B-O)") (class "Default")
      (node (ref "IC39") (pin "10") (pinfunction "I1_10") (pintype "input"))
      (node (ref "IC39") (pin "6") (pinfunction "O_6") (pintype "output"))
    )
    (net (code "194") (name "Net-(IC39D-I0)") (class "Default")
      (node (ref "IC39") (pin "12") (pinfunction "I0_12") (pintype "input"))
      (node (ref "IC7") (pin "11") (pinfunction "O_11") (pintype "output"))
    )
    (net (code "195") (name "Net-(IC39D-I1)") (class "Default")
      (node (ref "IC39") (pin "13") (pinfunction "I1_13") (pintype "input"))
      (node (ref "IC9") (pin "6") (pinfunction "O_6") (pintype "output"))
    )
    (net (code "196") (name "VCC") (class "Default")
      (node (ref "C1") (pin "1") (pinfunction "1_1") (pintype "passive"))
      (node (ref "C10") (pin "1") (pinfunction "1_1") (pintype "passive"))
      (node (ref "C11") (pin "1") (pinfunction "1_1") (pintype "passive"))
      (node (ref "C12") (pin "1") (pinfunction "1_1") (pintype "passive"))
      (node (ref "C13") (pin "1") (pinfunction "1_1") (pintype "passive"))
      (node (ref "C14") (pin "1") (pinfunction "1_1") (pintype "passive"))
      (node (ref "C15") (pin "1") (pinfunction "1_1") (pintype "passive"))
      (node (ref "C16") (pin "1") (pinfunction "1_1") (pintype "passive"))
      (node (ref "C17") (pin "1") (pinfunction "1_1") (pintype "passive"))
      (node (ref "C18") (pin "1") (pinfunction "1_1") (pintype "passive"))
      (node (ref "C19") (pin "1") (pinfunction "1_1") (pintype "passive"))
      (node (ref "C2") (pin "1") (pinfunction "1_1") (pintype "passive"))
      (node (ref "C20") (pin "1") (pinfunction "1_1") (pintype "passive"))
      (node (ref "C21") (pin "1") (pinfunction "1_1") (pintype "passive"))
      (node (ref "C22") (pin "1") (pinfunction "1_1") (pintype "passive"))
      (node (ref "C23") (pin "1") (pinfunction "1_1") (pintype "passive"))
      (node (ref "C24") (pin "1") (pinfunction "1_1") (pintype "passive"))
      (node (ref "C25") (pin "1") (pinfunction "1_1") (pintype "passive"))
      (node (ref "C26") (pin "1") (pinfunction "1_1") (pintype "passive"))
      (node (ref "C27") (pin "1") (pinfunction "1_1") (pintype "passive"))
      (node (ref "C28") (pin "1") (pinfunction "1_1") (pintype "passive"))
      (node (ref "C29") (pin "1") (pinfunction "1_1") (pintype "passive"))
      (node (ref "C3") (pin "1") (pinfunction "1_1") (pintype "passive"))
      (node (ref "C30") (pin "1") (pinfunction "1_1") (pintype "passive"))
      (node (ref "C31") (pin "1") (pinfunction "1_1") (pintype "passive"))
      (node (ref "C32") (pin "1") (pinfunction "1_1") (pintype "passive"))
      (node (ref "C33") (pin "1") (pinfunction "1_1") (pintype "passive"))
      (node (ref "C4") (pin "1") (pinfunction "1_1") (pintype "passive"))
      (node (ref "C5") (pin "1") (pinfunction "1_1") (pintype "passive"))
      (node (ref "C6") (pin "1") (pinfunction "1_1") (pintype "passive"))
      (node (ref "C7") (pin "1") (pinfunction "1_1") (pintype "passive"))
      (node (ref "C8") (pin "1") (pinfunction "1_1") (pintype "passive"))
      (node (ref "C9") (pin "1") (pinfunction "1_1") (pintype "passive"))
      (node (ref "D41") (pin "2") (pinfunction "A2_2") (pintype "passive"))
      (node (ref "D42") (pin "2") (pinfunction "A2_2") (pintype "passive"))
      (node (ref "D43") (pin "2") (pinfunction "A2_2") (pintype "passive"))
      (node (ref "D44") (pin "2") (pinfunction "A2_2") (pintype "passive"))
      (node (ref "D45") (pin "2") (pinfunction "A2_2") (pintype "passive"))
      (node (ref "D46") (pin "2") (pinfunction "A2_2") (pintype "passive"))
      (node (ref "D47") (pin "2") (pinfunction "A2_2") (pintype "passive"))
      (node (ref "D48") (pin "2") (pinfunction "A2_2") (pintype "passive"))
      (node (ref "D49") (pin "2") (pinfunction "A2_2") (pintype "passive"))
      (node (ref "D50") (pin "2") (pinfunction "A2_2") (pintype "passive"))
      (node (ref "D51") (pin "2") (pinfunction "A2_2") (pintype "passive"))
      (node (ref "D52") (pin "2") (pinfunction "A2_2") (pintype "passive"))
      (node (ref "D53") (pin "2") (pinfunction "A2_2") (pintype "passive"))
      (node (ref "D54") (pin "2") (pinfunction "A2_2") (pintype "passive"))
      (node (ref "D55") (pin "2") (pinfunction "A2_2") (pintype "passive"))
      (node (ref "D56") (pin "2") (pinfunction "A2_2") (pintype "passive"))
      (node (ref "IC1") (pin "16") (pinfunction "VCC_16") (pintype "power_in"))
      (node (ref "IC10") (pin "14") (pinfunction "VCC_14") (pintype "power_in"))
      (node (ref "IC11") (pin "14") (pinfunction "VCC_14") (pintype "power_in"))
      (node (ref "IC12") (pin "20") (pinfunction "VCC_20") (pintype "power_in"))
      (node (ref "IC13") (pin "14") (pinfunction "VCC_14") (pintype "power_in"))
      (node (ref "IC14") (pin "20") (pinfunction "VCC_20") (pintype "power_in"))
      (node (ref "IC15") (pin "20") (pinfunction "VCC_20") (pintype "power_in"))
      (node (ref "IC16") (pin "20") (pinfunction "VCC_20") (pintype "power_in"))
      (node (ref "IC17") (pin "14") (pinfunction "VCC_14") (pintype "power_in"))
      (node (ref "IC18") (pin "14") (pinfunction "VCC_14") (pintype "power_in"))
      (node (ref "IC19") (pin "14") (pinfunction "VCC_14") (pintype "power_in"))
      (node (ref "IC2") (pin "16") (pinfunction "VCC_16") (pintype "power_in"))
      (node (ref "IC20") (pin "14") (pinfunction "VCC_14") (pintype "power_in"))
      (node (ref "IC21") (pin "20") (pinfunction "VCC_20") (pintype "power_in"))
      (node (ref "IC22") (pin "20") (pinfunction "VCC_20") (pintype "power_in"))
      (node (ref "IC23") (pin "20") (pinfunction "VCC_20") (pintype "power_in"))
      (node (ref "IC24") (pin "20") (pinfunction "VCC_20") (pintype "power_in"))
      (node (ref "IC25") (pin "20") (pinfunction "VCC_20") (pintype "power_in"))
      (node (ref "IC3") (pin "24") (pinfunction "VCC_24") (pintype "power_in"))
      (node (ref "IC36") (pin "20") (pinfunction "VCC_20") (pintype "power_in"))
      (node (ref "IC37") (pin "14") (pinfunction "VCC_14") (pintype "power_in"))
      (node (ref "IC38") (pin "1") (pinfunction "DIR_1") (pintype "input"))
      (node (ref "IC38") (pin "20") (pinfunction "VCC_20") (pintype "power_in"))
      (node (ref "IC39") (pin "14") (pinfunction "VCC_14") (pintype "power_in"))
      (node (ref "IC4") (pin "14") (pinfunction "VCC_14") (pintype "power_in"))
      (node (ref "IC5") (pin "14") (pinfunction "VCC_14") (pintype "power_in"))
      (node (ref "IC6") (pin "14") (pinfunction "VCC_14") (pintype "power_in"))
      (node (ref "IC7") (pin "14") (pinfunction "VCC_14") (pintype "power_in"))
      (node (ref "IC8") (pin "13") (pinfunction "I_13") (pintype "input"))
      (node (ref "IC8") (pin "14") (pinfunction "VCC_14") (pintype "power_in"))
      (node (ref "IC9") (pin "12") (pinfunction "I0_12") (pintype "input"))
      (node (ref "IC9") (pin "14") (pinfunction "VCC_14") (pintype "power_in"))
      (node (ref "R40") (pin "2") (pinfunction "2_2") (pintype "passive"))
      (node (ref "SV_ALU_1") (pin "1") (pinfunction "1_1") (pintype "passive"))
      (node (ref "SV_ALU_1") (pin "36") (pinfunction "36_36") (pintype "passive"))
      (node (ref "SV_ALU_2") (pin "1") (pinfunction "1_1") (pintype "passive"))
      (node (ref "SV_ALU_2") (pin "36") (pinfunction "36_36") (pintype "passive"))
      (node (ref "SV_ALU_SUP1") (pin "1") (pinfunction "1_1") (pintype "passive"))
      (node (ref "SV_ALU_SUP1") (pin "3") (pinfunction "3_3") (pintype "passive"))
      (node (ref "SV_ALU_SUP1") (pin "5") (pinfunction "5_5") (pintype "passive"))
      (node (ref "SV_ALU_SUP2") (pin "1") (pinfunction "1_1") (pintype "passive"))
      (node (ref "SV_ALU_SUP2") (pin "3") (pinfunction "3_3") (pintype "passive"))
      (node (ref "SV_ALU_SUP2") (pin "5") (pinfunction "5_5") (pintype "passive"))
      (node (ref "SV_ALU_SUP3") (pin "1") (pinfunction "1_1") (pintype "passive"))
      (node (ref "SV_ALU_SUP3") (pin "3") (pinfunction "3_3") (pintype "passive"))
      (node (ref "SV_ALU_SUP3") (pin "5") (pinfunction "5_5") (pintype "passive"))
      (node (ref "SV_ALU_SUP4") (pin "1") (pinfunction "1_1") (pintype "passive"))
      (node (ref "SV_ALU_SUP4") (pin "3") (pinfunction "3_3") (pintype "passive"))
      (node (ref "SV_ALU_SUP4") (pin "5") (pinfunction "5_5") (pintype "passive"))
      (node (ref "SV_ALU_SUP5") (pin "1") (pinfunction "1_1") (pintype "passive"))
      (node (ref "SV_ALU_SUP5") (pin "3") (pinfunction "3_3") (pintype "passive"))
      (node (ref "SV_ALU_SUP5") (pin "5") (pinfunction "5_5") (pintype "passive"))
      (node (ref "SV_ALU_SUP6") (pin "1") (pinfunction "1_1") (pintype "passive"))
      (node (ref "SV_ALU_SUP6") (pin "3") (pinfunction "3_3") (pintype "passive"))
      (node (ref "SV_ALU_SUP6") (pin "5") (pinfunction "5_5") (pintype "passive"))
    )
    (net (code "197") (name "unconnected-(IC8F-O-Pad12)") (class "Default")
      (node (ref "IC8") (pin "12") (pinfunction "O_12") (pintype "output"))
    )
    (net (code "198") (name "unconnected-(IC9C-O-Pad8)") (class "Default")
      (node (ref "IC9") (pin "8") (pinfunction "O_8") (pintype "output"))
    )
    (net (code "199") (name "unconnected-(IC9D-O-Pad11)") (class "Default")
      (node (ref "IC9") (pin "11") (pinfunction "O_11") (pintype "output"))
    )
    (net (code "200") (name "unconnected-(IC21A-B2-Pad17)") (class "Default")
      (node (ref "IC21") (pin "17") (pinfunction "B2_17") (pintype "bidirectional"))
    )
    (net (code "201") (name "unconnected-(IC21A-B3-Pad16)") (class "Default")
      (node (ref "IC21") (pin "16") (pinfunction "B3_16") (pintype "bidirectional"))
    )
    (net (code "202") (name "unconnected-(IC21A-B4-Pad15)") (class "Default")
      (node (ref "IC21") (pin "15") (pinfunction "B4_15") (pintype "bidirectional"))
    )
    (net (code "203") (name "unconnected-(IC21A-B5-Pad14)") (class "Default")
      (node (ref "IC21") (pin "14") (pinfunction "B5_14") (pintype "bidirectional"))
    )
    (net (code "204") (name "unconnected-(IC21A-B6-Pad13)") (class "Default")
      (node (ref "IC21") (pin "13") (pinfunction "B6_13") (pintype "bidirectional"))
    )
    (net (code "205") (name "unconnected-(IC21A-B7-Pad12)") (class "Default")
      (node (ref "IC21") (pin "12") (pinfunction "B7_12") (pintype "bidirectional"))
    )
    (net (code "206") (name "unconnected-(IC21A-B8-Pad11)") (class "Default")
      (node (ref "IC21") (pin "11") (pinfunction "B8_11") (pintype "bidirectional"))
    )
    (net (code "207") (name "unconnected-(SV_ALU_1-Pad4)") (class "Default")
      (node (ref "SV_ALU_1") (pin "4") (pinfunction "4_4") (pintype "passive"))
    )
    (net (code "208") (name "unconnected-(SV_ALU_1-Pad6)") (class "Default")
      (node (ref "SV_ALU_1") (pin "6") (pinfunction "6_6") (pintype "passive"))
    )
    (net (code "209") (name "unconnected-(SV_ALU_1-Pad8)") (class "Default")
      (node (ref "SV_ALU_1") (pin "8") (pinfunction "8_8") (pintype "passive"))
    )
    (net (code "210") (name "unconnected-(SV_ALU_1-Pad10)") (class "Default")
      (node (ref "SV_ALU_1") (pin "10") (pinfunction "10_10") (pintype "passive"))
    )
    (net (code "211") (name "unconnected-(SV_ALU_1-Pad12)") (class "Default")
      (node (ref "SV_ALU_1") (pin "12") (pinfunction "12_12") (pintype "passive"))
    )
    (net (code "212") (name "unconnected-(SV_ALU_1-Pad14)") (class "Default")
      (node (ref "SV_ALU_1") (pin "14") (pinfunction "14_14") (pintype "passive"))
    )
    (net (code "213") (name "unconnected-(SV_ALU_1-Pad16)") (class "Default")
      (node (ref "SV_ALU_1") (pin "16") (pinfunction "16_16") (pintype "passive"))
    )
    (net (code "214") (name "unconnected-(SV_ALU_1-Pad18)") (class "Default")
      (node (ref "SV_ALU_1") (pin "18") (pinfunction "18_18") (pintype "passive"))
    )
    (net (code "215") (name "unconnected-(SV_ALU_1-Pad20)") (class "Default")
      (node (ref "SV_ALU_1") (pin "20") (pinfunction "20_20") (pintype "passive"))
    )
    (net (code "216") (name "unconnected-(SV_ALU_1-Pad22)") (class "Default")
      (node (ref "SV_ALU_1") (pin "22") (pinfunction "22_22") (pintype "passive"))
    )
    (net (code "217") (name "unconnected-(SV_ALU_1-Pad24)") (class "Default")
      (node (ref "SV_ALU_1") (pin "24") (pinfunction "24_24") (pintype "passive"))
    )
    (net (code "218") (name "unconnected-(SV_ALU_1-Pad26)") (class "Default")
      (node (ref "SV_ALU_1") (pin "26") (pinfunction "26_26") (pintype "passive"))
    )
    (net (code "219") (name "unconnected-(SV_ALU_2-Pad4)") (class "Default")
      (node (ref "SV_ALU_2") (pin "4") (pinfunction "4_4") (pintype "passive"))
    )
    (net (code "220") (name "unconnected-(SV_ALU_2-Pad6)") (class "Default")
      (node (ref "SV_ALU_2") (pin "6") (pinfunction "6_6") (pintype "passive"))
    )
    (net (code "221") (name "unconnected-(SV_ALU_2-Pad8)") (class "Default")
      (node (ref "SV_ALU_2") (pin "8") (pinfunction "8_8") (pintype "passive"))
    )
    (net (code "222") (name "unconnected-(SV_ALU_2-Pad10)") (class "Default")
      (node (ref "SV_ALU_2") (pin "10") (pinfunction "10_10") (pintype "passive"))
    )
    (net (code "223") (name "unconnected-(SV_ALU_2-Pad12)") (class "Default")
      (node (ref "SV_ALU_2") (pin "12") (pinfunction "12_12") (pintype "passive"))
    )
    (net (code "224") (name "unconnected-(SV_ALU_2-Pad14)") (class "Default")
      (node (ref "SV_ALU_2") (pin "14") (pinfunction "14_14") (pintype "passive"))
    )
    (net (code "225") (name "unconnected-(SV_ALU_2-Pad16)") (class "Default")
      (node (ref "SV_ALU_2") (pin "16") (pinfunction "16_16") (pintype "passive"))
    )
    (net (code "226") (name "unconnected-(SV_ALU_2-Pad18)") (class "Default")
      (node (ref "SV_ALU_2") (pin "18") (pinfunction "18_18") (pintype "passive"))
    )
    (net (code "227") (name "unconnected-(SV_ALU_2-Pad19)") (class "Default")
      (node (ref "SV_ALU_2") (pin "19") (pinfunction "19_19") (pintype "passive"))
    )
    (net (code "228") (name "unconnected-(SV_ALU_2-Pad20)") (class "Default")
      (node (ref "SV_ALU_2") (pin "20") (pinfunction "20_20") (pintype "passive"))
    )
    (net (code "229") (name "unconnected-(SV_ALU_2-Pad21)") (class "Default")
      (node (ref "SV_ALU_2") (pin "21") (pinfunction "21_21") (pintype "passive"))
    )
    (net (code "230") (name "unconnected-(SV_ALU_2-Pad22)") (class "Default")
      (node (ref "SV_ALU_2") (pin "22") (pinfunction "22_22") (pintype "passive"))
    )
    (net (code "231") (name "unconnected-(SV_ALU_2-Pad34)") (class "Default")
      (node (ref "SV_ALU_2") (pin "34") (pinfunction "34_34") (pintype "passive"))
    )
  )
)
